# bontor_mbed_lowpan_rev_g.net
KiCad netlist of a schematic drawn in EAGLE
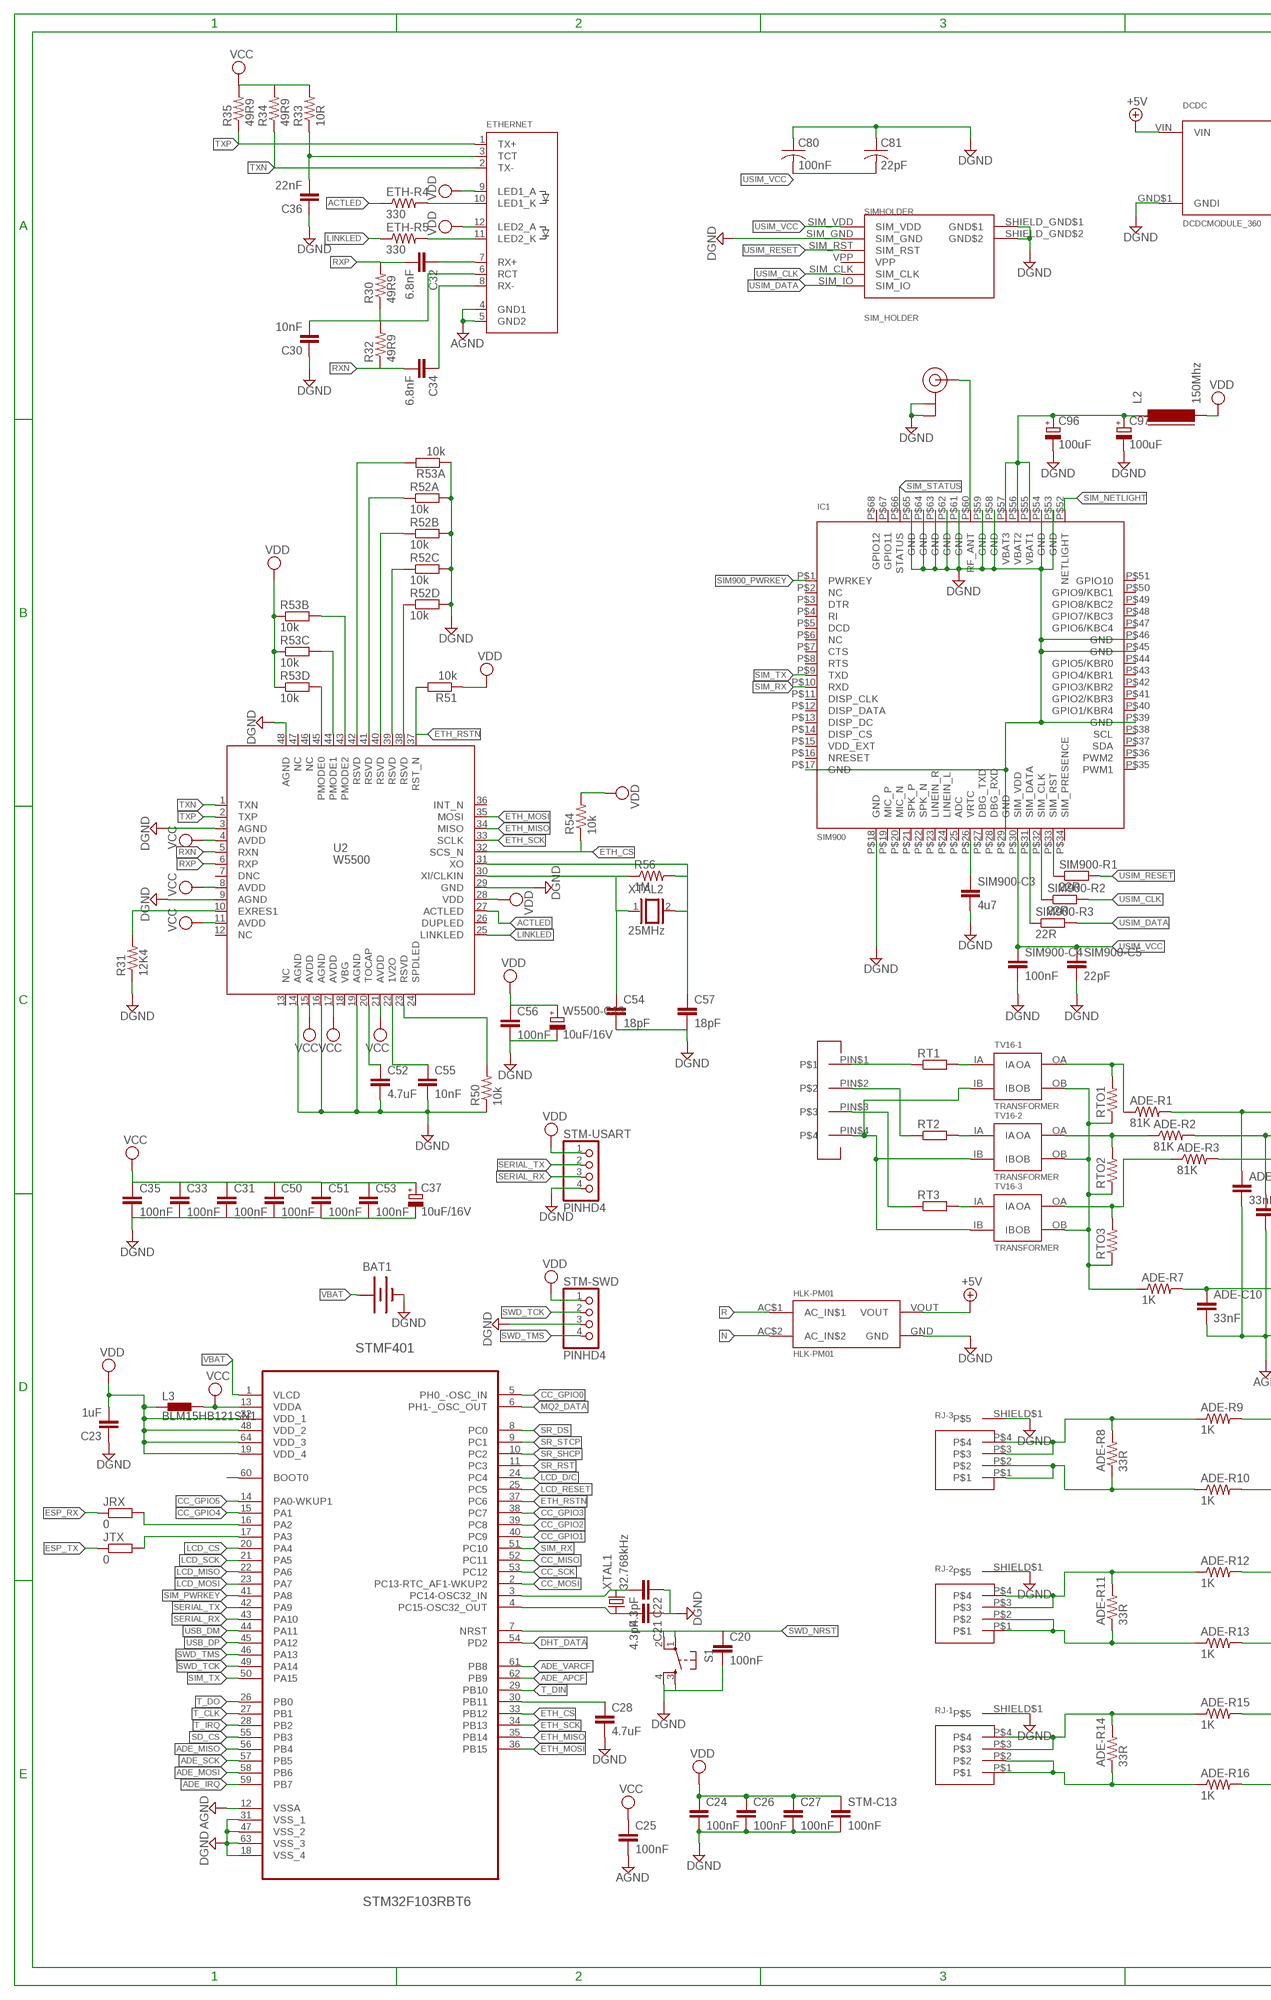
[diagram p0: schematic, sheet 1, part 1 of 2]
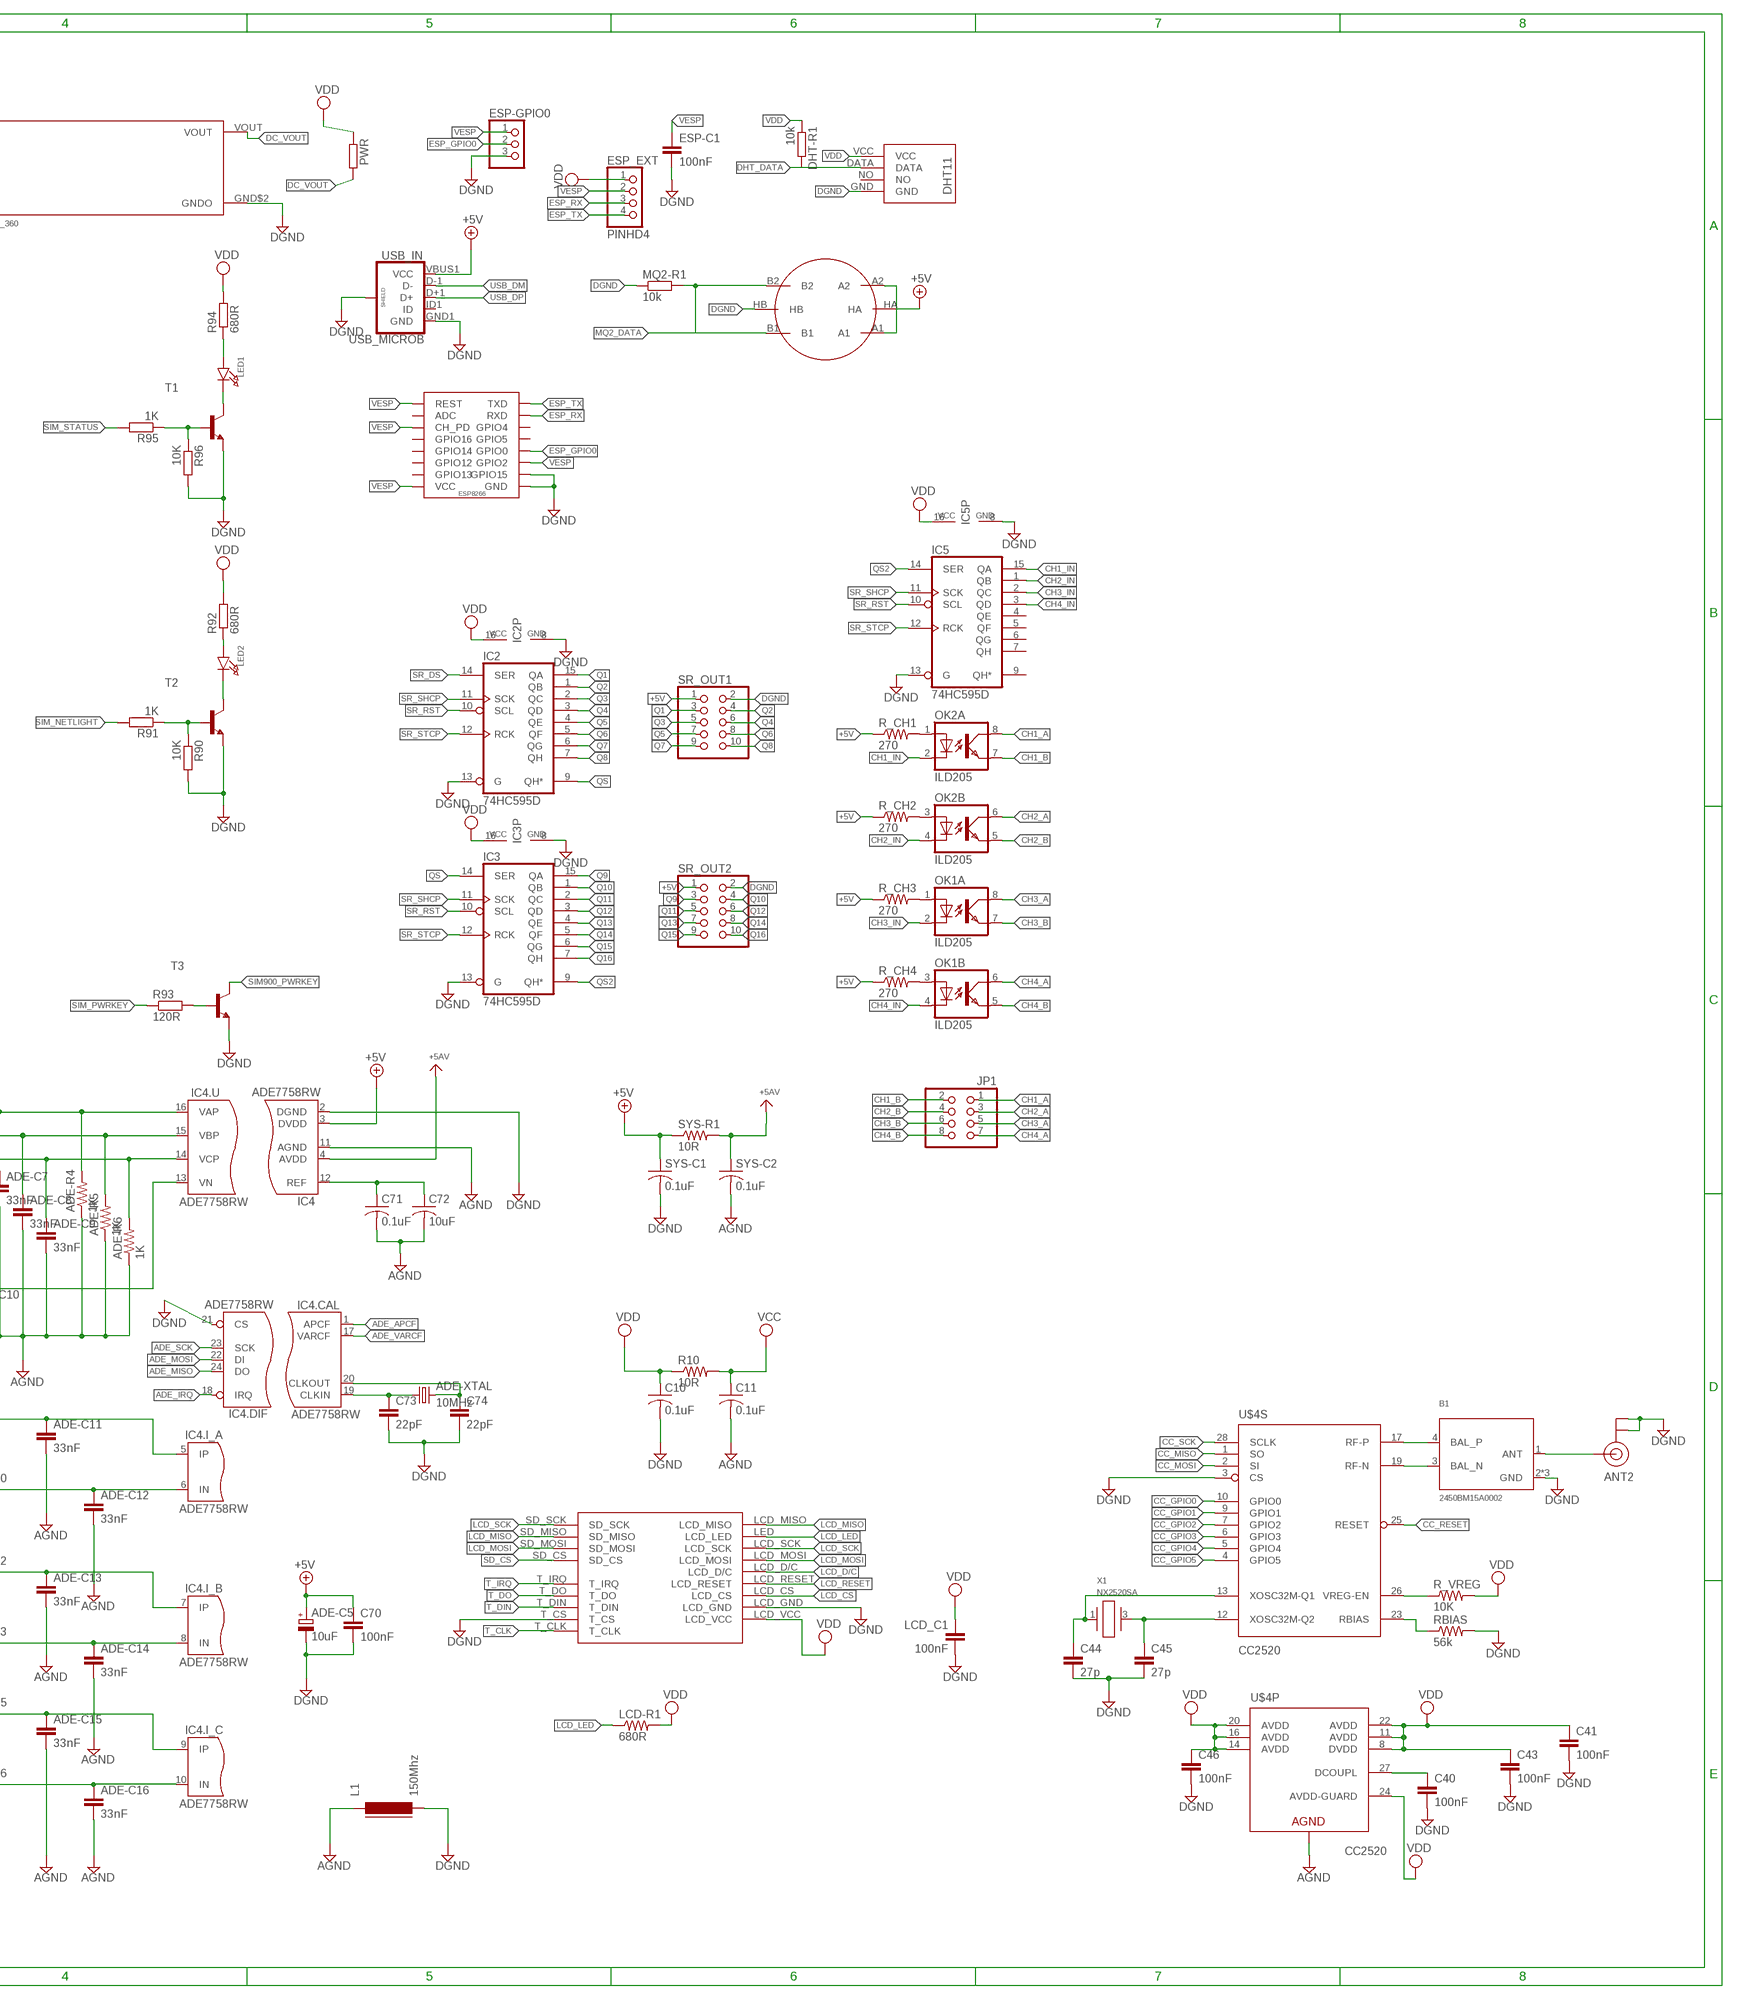
[diagram p1: schematic, sheet 1, part 2 of 2]

(export (version "E")
  (design (tool "Eeschema 10.0.6"))
  (components
    (comp (ref "ADE-C5")
      (value "10uF")
      (footprint "eagle-import:153CLV-0605")
      (libsource (lib "eagle-import") (part "CPOL-EU153CLV-0605"))
    )
    (comp (ref "ADE-C7")
      (value "33nF")
      (footprint "eagle-import:0603-CAP")
      (libsource (lib "eagle-import") (part "CAP0603-CAP"))
    )
    (comp (ref "ADE-C8")
      (value "33nF")
      (footprint "eagle-import:0603-CAP")
      (libsource (lib "eagle-import") (part "CAP0603-CAP"))
    )
    (comp (ref "ADE-C9")
      (value "33nF")
      (footprint "eagle-import:0603-CAP")
      (libsource (lib "eagle-import") (part "CAP0603-CAP"))
    )
    (comp (ref "ADE-C10")
      (value "33nF")
      (footprint "eagle-import:0603-CAP")
      (libsource (lib "eagle-import") (part "CAP0603-CAP"))
    )
    (comp (ref "ADE-C11")
      (value "33nF")
      (footprint "eagle-import:0402-CAP")
      (libsource (lib "eagle-import") (part "CAP0402-CAP"))
    )
    (comp (ref "ADE-C12")
      (value "33nF")
      (footprint "eagle-import:0402-CAP")
      (libsource (lib "eagle-import") (part "CAP0402-CAP"))
    )
    (comp (ref "ADE-C13")
      (value "33nF")
      (footprint "eagle-import:0402-CAP")
      (libsource (lib "eagle-import") (part "CAP0402-CAP"))
    )
    (comp (ref "ADE-C14")
      (value "33nF")
      (footprint "eagle-import:0402-CAP")
      (libsource (lib "eagle-import") (part "CAP0402-CAP"))
    )
    (comp (ref "ADE-C15")
      (value "33nF")
      (footprint "eagle-import:0402-CAP")
      (libsource (lib "eagle-import") (part "CAP0402-CAP"))
    )
    (comp (ref "ADE-C16")
      (value "33nF")
      (footprint "eagle-import:0402-CAP")
      (libsource (lib "eagle-import") (part "CAP0402-CAP"))
    )
    (comp (ref "ADE-R1")
      (value "81K")
      (footprint "eagle-import:0603-RES")
      (libsource (lib "eagle-import") (part "RESISTOR0603-RES"))
    )
    (comp (ref "ADE-R2")
      (value "81K")
      (footprint "eagle-import:0603-RES")
      (libsource (lib "eagle-import") (part "RESISTOR0603-RES"))
    )
    (comp (ref "ADE-R3")
      (value "81K")
      (footprint "eagle-import:0603-RES")
      (libsource (lib "eagle-import") (part "RESISTOR0603-RES"))
    )
    (comp (ref "ADE-R4")
      (value "1K")
      (footprint "eagle-import:0603-RES")
      (libsource (lib "eagle-import") (part "RESISTOR0603-RES"))
    )
    (comp (ref "ADE-R5")
      (value "1K")
      (footprint "eagle-import:0603-RES")
      (libsource (lib "eagle-import") (part "RESISTOR0603-RES"))
    )
    (comp (ref "ADE-R6")
      (value "1K")
      (footprint "eagle-import:0603-RES")
      (libsource (lib "eagle-import") (part "RESISTOR0603-RES"))
    )
    (comp (ref "ADE-R7")
      (value "1K")
      (footprint "eagle-import:0603-RES")
      (libsource (lib "eagle-import") (part "RESISTOR0603-RES"))
    )
    (comp (ref "ADE-R8")
      (value "33R")
      (footprint "eagle-import:0402-RES")
      (libsource (lib "eagle-import") (part "RESISTOR0402-RES"))
    )
    (comp (ref "ADE-R9")
      (value "1K")
      (footprint "eagle-import:0402-RES")
      (libsource (lib "eagle-import") (part "RESISTOR0402-RES"))
    )
    (comp (ref "ADE-R10")
      (value "1K")
      (footprint "eagle-import:0402-RES")
      (libsource (lib "eagle-import") (part "RESISTOR0402-RES"))
    )
    (comp (ref "ADE-R11")
      (value "33R")
      (footprint "eagle-import:0402-RES")
      (libsource (lib "eagle-import") (part "RESISTOR0402-RES"))
    )
    (comp (ref "ADE-R12")
      (value "1K")
      (footprint "eagle-import:0402-RES")
      (libsource (lib "eagle-import") (part "RESISTOR0402-RES"))
    )
    (comp (ref "ADE-R13")
      (value "1K")
      (footprint "eagle-import:0402-RES")
      (libsource (lib "eagle-import") (part "RESISTOR0402-RES"))
    )
    (comp (ref "ADE-R14")
      (value "33R")
      (footprint "eagle-import:0402-RES")
      (libsource (lib "eagle-import") (part "RESISTOR0402-RES"))
    )
    (comp (ref "ADE-R15")
      (value "1K")
      (footprint "eagle-import:0402-RES")
      (libsource (lib "eagle-import") (part "RESISTOR0402-RES"))
    )
    (comp (ref "ADE-R16")
      (value "1K")
      (footprint "eagle-import:0402-RES")
      (libsource (lib "eagle-import") (part "RESISTOR0402-RES"))
    )
    (comp (ref "ADE-XTAL")
      (value "10MHz")
      (footprint "eagle-import:HC49US")
      (libsource (lib "eagle-import") (part "CRYSTALHC49US"))
    )
    (comp (ref "ANT1")
      (value "U.FL")
      (footprint "eagle-import:U.FL")
      (libsource (lib "eagle-import") (part "U.FL"))
    )
    (comp (ref "ANT2")
      (value "U.FL")
      (footprint "eagle-import:U.FL")
      (libsource (lib "eagle-import") (part "SparkFun-Connectors_U.FL"))
    )
    (comp (ref "B1")
      (value "2450BM15A0002")
      (footprint "eagle-import:2450BM")
      (libsource (lib "eagle-import") (part "2450BM15A0002"))
    )
    (comp (ref "BAT1")
      (value "BATTERY12MM")
      (footprint "eagle-import:BATTCON_12MM")
      (libsource (lib "eagle-import") (part "BATTERY12MM"))
    )
    (comp (ref "C10")
      (value "0.1uF")
      (footprint "eagle-import:C0603@1")
      (libsource (lib "eagle-import") (part "C-USC0603"))
    )
    (comp (ref "C11")
      (value "0.1uF")
      (footprint "eagle-import:C0603@1")
      (libsource (lib "eagle-import") (part "C-USC0603"))
    )
    (comp (ref "C20")
      (value "100nF")
      (footprint "eagle-import:C0603")
      (libsource (lib "eagle-import") (part "C-EUC0603"))
    )
    (comp (ref "C21")
      (value "4.3pF")
      (footprint "eagle-import:C0603")
      (libsource (lib "eagle-import") (part "C-EUC0603"))
    )
    (comp (ref "C22")
      (value "4.3pF")
      (footprint "eagle-import:C0603")
      (libsource (lib "eagle-import") (part "C-EUC0603"))
    )
    (comp (ref "C23")
      (value "1uF")
      (footprint "eagle-import:C0603")
      (libsource (lib "eagle-import") (part "C-EUC0603"))
    )
    (comp (ref "C24")
      (value "100nF")
      (footprint "eagle-import:C0603")
      (libsource (lib "eagle-import") (part "C-EUC0603"))
    )
    (comp (ref "C25")
      (value "100nF")
      (footprint "eagle-import:C0603")
      (libsource (lib "eagle-import") (part "C-EUC0603"))
    )
    (comp (ref "C26")
      (value "100nF")
      (footprint "eagle-import:C0603")
      (libsource (lib "eagle-import") (part "C-EUC0603"))
    )
    (comp (ref "C27")
      (value "100nF")
      (footprint "eagle-import:C0402")
      (libsource (lib "eagle-import") (part "C-EUC0402"))
    )
    (comp (ref "C28")
      (value "4.7uF")
      (footprint "eagle-import:C0603")
      (libsource (lib "eagle-import") (part "C-EUC0603"))
    )
    (comp (ref "C30")
      (value "10nF")
      (footprint "eagle-import:C0603")
      (libsource (lib "eagle-import") (part "C-EUC0603"))
    )
    (comp (ref "C31")
      (value "100nF")
      (footprint "eagle-import:C0603")
      (libsource (lib "eagle-import") (part "C-EUC0603"))
    )
    (comp (ref "C32")
      (value "6.8nF")
      (footprint "eagle-import:C0603")
      (libsource (lib "eagle-import") (part "C-EUC0603"))
    )
    (comp (ref "C33")
      (value "100nF")
      (footprint "eagle-import:C0603")
      (libsource (lib "eagle-import") (part "C-EUC0603"))
    )
    (comp (ref "C34")
      (value "6.8nF")
      (footprint "eagle-import:C0603")
      (libsource (lib "eagle-import") (part "C-EUC0603"))
    )
    (comp (ref "C35")
      (value "100nF")
      (footprint "eagle-import:C0603")
      (libsource (lib "eagle-import") (part "C-EUC0603"))
    )
    (comp (ref "C36")
      (value "22nF")
      (footprint "eagle-import:C0603")
      (libsource (lib "eagle-import") (part "C-EUC0603"))
    )
    (comp (ref "C37")
      (value "10uF/16V")
      (footprint "eagle-import:153CLV-0605")
      (libsource (lib "eagle-import") (part "CPOL-EU153CLV-0605"))
    )
    (comp (ref "C40")
      (value "100nF")
      (footprint "eagle-import:C0402")
      (libsource (lib "eagle-import") (part "C-EUC0402"))
    )
    (comp (ref "C41")
      (value "100nF")
      (footprint "eagle-import:C0402")
      (libsource (lib "eagle-import") (part "C-EUC0402"))
    )
    (comp (ref "C43")
      (value "100nF")
      (footprint "eagle-import:C0402")
      (libsource (lib "eagle-import") (part "C-EUC0402"))
    )
    (comp (ref "C44")
      (value "27p")
      (footprint "eagle-import:C0201")
      (libsource (lib "eagle-import") (part "C-EUC0201"))
    )
    (comp (ref "C45")
      (value "27p")
      (footprint "eagle-import:C0201")
      (libsource (lib "eagle-import") (part "C-EUC0201"))
    )
    (comp (ref "C46")
      (value "100nF")
      (footprint "eagle-import:C0402")
      (libsource (lib "eagle-import") (part "C-EUC0402"))
    )
    (comp (ref "C50")
      (value "100nF")
      (footprint "eagle-import:C0603")
      (libsource (lib "eagle-import") (part "C-EUC0603"))
    )
    (comp (ref "C51")
      (value "100nF")
      (footprint "eagle-import:C0603")
      (libsource (lib "eagle-import") (part "C-EUC0603"))
    )
    (comp (ref "C52")
      (value "4.7uF")
      (footprint "eagle-import:C0603")
      (libsource (lib "eagle-import") (part "C-EUC0603"))
    )
    (comp (ref "C53")
      (value "100nF")
      (footprint "eagle-import:C0603")
      (libsource (lib "eagle-import") (part "C-EUC0603"))
    )
    (comp (ref "C54")
      (value "18pF")
      (footprint "eagle-import:C0603")
      (libsource (lib "eagle-import") (part "C-EUC0603"))
    )
    (comp (ref "C55")
      (value "10nF")
      (footprint "eagle-import:C0603")
      (libsource (lib "eagle-import") (part "C-EUC0603"))
    )
    (comp (ref "C56")
      (value "100nF")
      (footprint "eagle-import:C0603")
      (libsource (lib "eagle-import") (part "C-EUC0603"))
    )
    (comp (ref "C57")
      (value "18pF")
      (footprint "eagle-import:C0603")
      (libsource (lib "eagle-import") (part "C-EUC0603"))
    )
    (comp (ref "C70")
      (value "100nF")
      (footprint "eagle-import:C0603")
      (libsource (lib "eagle-import") (part "C-EUC0603"))
    )
    (comp (ref "C71")
      (value "0.1uF")
      (footprint "eagle-import:C0603@1")
      (libsource (lib "eagle-import") (part "C-USC0603"))
    )
    (comp (ref "C72")
      (value "10uF")
      (footprint "eagle-import:C0805K")
      (libsource (lib "eagle-import") (part "C-USC0805K"))
    )
    (comp (ref "C73")
      (value "22pF")
      (footprint "eagle-import:C0603")
      (libsource (lib "eagle-import") (part "C-EUC0603"))
    )
    (comp (ref "C74")
      (value "22pF")
      (footprint "eagle-import:C0603")
      (libsource (lib "eagle-import") (part "C-EUC0603"))
    )
    (comp (ref "C80")
      (value "100nF")
      (footprint "eagle-import:C0603K")
      (libsource (lib "eagle-import") (part "C-USC0603K"))
    )
    (comp (ref "C81")
      (value "22pF")
      (footprint "eagle-import:C0603K")
      (libsource (lib "eagle-import") (part "C-USC0603K"))
    )
    (comp (ref "C96")
      (value "100uF")
      (footprint "eagle-import:153CLV-0605")
      (libsource (lib "eagle-import") (part "CPOL-EU153CLV-0605"))
    )
    (comp (ref "C97")
      (value "100uF")
      (footprint "eagle-import:153CLV-0605")
      (libsource (lib "eagle-import") (part "CPOL-EU153CLV-0605"))
    )
    (comp (ref "DCDC")
      (value "DCDCMODULE_360")
      (footprint "eagle-import:DCDCMODULE-360")
      (libsource (lib "eagle-import") (part "DCDCMODULE_360"))
    )
    (comp (ref "DHT-R1")
      (value "10k")
      (footprint "eagle-import:R0603")
      (libsource (lib "eagle-import") (part "resistor_R-EU_R0603"))
    )
    (comp (ref "ESP")
      (value "ESP")
      (footprint "eagle-import:WI12")
      (libsource (lib "eagle-import") (part "ESP8266WI12"))
    )
    (comp (ref "ESP-C1")
      (value "100nF")
      (footprint "eagle-import:C0603")
      (libsource (lib "eagle-import") (part "C-EUC0603"))
    )
    (comp (ref "ESP-GPIO0")
      (value "PINHD-1X3")
      (footprint "eagle-import:1X03")
      (libsource (lib "eagle-import") (part "PINHD-1X3"))
    )
    (comp (ref "ESP_EXT")
      (value "PINHD4")
      (footprint "eagle-import:PINHD4")
      (libsource (lib "eagle-import") (part "PINHD4"))
    )
    (comp (ref "ETH-R4")
      (value "330")
      (footprint "eagle-import:R0603")
      (libsource (lib "eagle-import") (part "resistor_R-US_R0603"))
    )
    (comp (ref "ETH-R5")
      (value "330")
      (footprint "eagle-import:R0603")
      (libsource (lib "eagle-import") (part "resistor_R-US_R0603"))
    )
    (comp (ref "ETHERNET")
      (value "RJ45J0026D21BNL")
      (footprint "eagle-import:RJ45_PULSEJACK")
      (libsource (lib "eagle-import") (part "RJ45J0026D21BNL"))
    )
    (comp (ref "HLK-PM01")
      (value "HLK-PM01")
      (footprint "eagle-import:HLK-PM01")
      (libsource (lib "eagle-import") (part "HLK-PM01"))
    )
    (comp (ref "IC1")
      (value "SIM900")
      (footprint "eagle-import:SIM900_SMT")
      (libsource (lib "eagle-import") (part "GSM_SIM900_LITERAL"))
    )
    (comp (ref "IC2")
      (value "74HC595D")
      (footprint "eagle-import:SO16")
      (libsource (lib "eagle-import") (part "74595DHC"))
    )
    (comp (ref "IC3")
      (value "74HC595D")
      (footprint "eagle-import:SO16")
      (libsource (lib "eagle-import") (part "74595DHC"))
    )
    (comp (ref "IC4")
      (value "ADE7758RW")
      (footprint "eagle-import:SOIC24")
      (libsource (lib "eagle-import") (part "ADE7758RW"))
    )
    (comp (ref "IC5")
      (value "74HC595D")
      (footprint "eagle-import:SO16")
      (libsource (lib "eagle-import") (part "74595DHC"))
    )
    (comp (ref "JP1")
      (value "PINHD-2X4")
      (footprint "eagle-import:2X04")
      (libsource (lib "eagle-import") (part "PINHD-2X4"))
    )
    (comp (ref "JRX")
      (value "0")
      (footprint "eagle-import:R0201")
      (libsource (lib "eagle-import") (part "R-EU_R0201"))
    )
    (comp (ref "JTX")
      (value "0")
      (footprint "eagle-import:R0201")
      (libsource (lib "eagle-import") (part "R-EU_R0201"))
    )
    (comp (ref "L1")
      (value "150Mhz")
      (footprint "eagle-import:FB805")
      (libsource (lib "eagle-import") (part "FERRITE-0805"))
    )
    (comp (ref "L2")
      (value "150Mhz")
      (footprint "eagle-import:FB805")
      (libsource (lib "eagle-import") (part "FERRITE-0805"))
    )
    (comp (ref "L3")
      (value "BLM15HB121SN1")
      (footprint "eagle-import:0402")
      (libsource (lib "eagle-import") (part "BLM15HB121SN1"))
    )
    (comp (ref "LCD-R1")
      (value "680R")
      (footprint "eagle-import:0603-RES")
      (libsource (lib "eagle-import") (part "RESISTOR0603-RES"))
    )
    (comp (ref "LCD14")
      (value "LCD_2.4")
      (footprint "eagle-import:LCD_TOUCH_2-4")
      (libsource (lib "eagle-import") (part "LCD_2.4"))
    )
    (comp (ref "LCD_C1")
      (value "100nF")
      (footprint "eagle-import:C0603")
      (libsource (lib "eagle-import") (part "C-EUC0603"))
    )
    (comp (ref "LED1")
      (value "LED0805_NOOUTLINE")
      (footprint "eagle-import:CHIPLED_0805_NOOUTLINE")
      (libsource (lib "eagle-import") (part "LED0805_NOOUTLINE"))
    )
    (comp (ref "LED2")
      (value "LED0805_NOOUTLINE")
      (footprint "eagle-import:CHIPLED_0805_NOOUTLINE")
      (libsource (lib "eagle-import") (part "LED0805_NOOUTLINE"))
    )
    (comp (ref "MQ2-R1")
      (value "10k")
      (footprint "eagle-import:R0603")
      (libsource (lib "eagle-import") (part "resistor_R-EU_R0603"))
    )
    (comp (ref "OK1")
      (value "ILD205")
      (footprint "eagle-import:SOIC08")
      (fields (field (name "MF") "VISHAY/TELEFUNKEN") (field (name "MPN") "ILD205T"))
      (libsource (lib "eagle-import") (part "ILD205"))
    )
    (comp (ref "OK2")
      (value "ILD205")
      (footprint "eagle-import:SOIC08")
      (fields (field (name "MF") "VISHAY/TELEFUNKEN") (field (name "MPN") "ILD205T"))
      (libsource (lib "eagle-import") (part "ILD205"))
    )
    (comp (ref "PWR")
      (value "R-EU_R0402")
      (footprint "eagle-import:R0402")
      (libsource (lib "eagle-import") (part "R-EU_R0402"))
    )
    (comp (ref "R10")
      (value "10R")
      (footprint "eagle-import:0603-RES")
      (libsource (lib "eagle-import") (part "RESISTOR0603-RES"))
    )
    (comp (ref "R30")
      (value "49R9")
      (footprint "eagle-import:R0603")
      (libsource (lib "eagle-import") (part "resistor_R-US_R0603"))
    )
    (comp (ref "R31")
      (value "12K4")
      (footprint "eagle-import:R0805")
      (libsource (lib "eagle-import") (part "resistor_R-US_R0805"))
    )
    (comp (ref "R32")
      (value "49R9")
      (footprint "eagle-import:R0603")
      (libsource (lib "eagle-import") (part "resistor_R-US_R0603"))
    )
    (comp (ref "R33")
      (value "10R")
      (footprint "eagle-import:R0603")
      (libsource (lib "eagle-import") (part "resistor_R-US_R0603"))
    )
    (comp (ref "R34")
      (value "49R9")
      (footprint "eagle-import:R0603")
      (libsource (lib "eagle-import") (part "resistor_R-US_R0603"))
    )
    (comp (ref "R35")
      (value "49R9")
      (footprint "eagle-import:R0603")
      (libsource (lib "eagle-import") (part "resistor_R-US_R0603"))
    )
    (comp (ref "R50")
      (value "10k")
      (footprint "eagle-import:R0603")
      (libsource (lib "eagle-import") (part "resistor_R-US_R0603"))
    )
    (comp (ref "R51")
      (value "10k")
      (footprint "eagle-import:R0603")
      (libsource (lib "eagle-import") (part "R-EU_R0603"))
    )
    (comp (ref "R52")
      (value "10k")
      (footprint "eagle-import:RN8P-4R-CRA06S")
      (libsource (lib "eagle-import") (part "RESISTOR_ARRAY_4"))
    )
    (comp (ref "R53")
      (value "10k")
      (footprint "eagle-import:RN8P-4R-CRA06S")
      (libsource (lib "eagle-import") (part "RESISTOR_ARRAY_4"))
    )
    (comp (ref "R54")
      (value "10k")
      (footprint "eagle-import:R0603")
      (libsource (lib "eagle-import") (part "resistor_R-US_R0603"))
    )
    (comp (ref "R56")
      (value "1M")
      (footprint "eagle-import:R0603")
      (libsource (lib "eagle-import") (part "resistor_R-US_R0603"))
    )
    (comp (ref "R90")
      (value "10K")
      (footprint "eagle-import:R0603")
      (libsource (lib "eagle-import") (part "R-EU_R0603"))
    )
    (comp (ref "R91")
      (value "1K")
      (footprint "eagle-import:R0603")
      (libsource (lib "eagle-import") (part "R-EU_R0603"))
    )
    (comp (ref "R92")
      (value "680R")
      (footprint "eagle-import:R0603")
      (libsource (lib "eagle-import") (part "R-EU_R0603"))
    )
    (comp (ref "R93")
      (value "120R")
      (footprint "eagle-import:R0603")
      (libsource (lib "eagle-import") (part "resistor_R-EU_R0603"))
    )
    (comp (ref "R94")
      (value "680R")
      (footprint "eagle-import:R0603")
      (libsource (lib "eagle-import") (part "R-EU_R0603"))
    )
    (comp (ref "R95")
      (value "1K")
      (footprint "eagle-import:R0603")
      (libsource (lib "eagle-import") (part "R-EU_R0603"))
    )
    (comp (ref "R96")
      (value "10K")
      (footprint "eagle-import:R0603")
      (libsource (lib "eagle-import") (part "R-EU_R0603"))
    )
    (comp (ref "RBIAS")
      (value "56k")
      (footprint "eagle-import:0402-RES")
      (libsource (lib "eagle-import") (part "RESISTOR0402-RES"))
    )
    (comp (ref "RJ-1")
      (value "RJ11-4P-V")
      (footprint "eagle-import:RJ11-4P-V")
      (libsource (lib "eagle-import") (part "RJ11-4P-V"))
    )
    (comp (ref "RJ-2")
      (value "RJ11-4P-V")
      (footprint "eagle-import:RJ11-4P-V")
      (libsource (lib "eagle-import") (part "RJ11-4P-V"))
    )
    (comp (ref "RJ-3")
      (value "RJ11-4P-V")
      (footprint "eagle-import:RJ11-4P-V")
      (libsource (lib "eagle-import") (part "RJ11-4P-V"))
    )
    (comp (ref "RT1")
      (value "R-EU_0309/V")
      (footprint "eagle-import:0309V")
      (libsource (lib "eagle-import") (part "R-EU_0309/V"))
    )
    (comp (ref "RT2")
      (value "R-EU_0309/V")
      (footprint "eagle-import:0309V")
      (libsource (lib "eagle-import") (part "R-EU_0309/V"))
    )
    (comp (ref "RT3")
      (value "R-EU_0309/V")
      (footprint "eagle-import:0309V")
      (libsource (lib "eagle-import") (part "R-EU_0309/V"))
    )
    (comp (ref "RTO1")
      (value "R-US_0309_12")
      (footprint "eagle-import:0309_12")
      (libsource (lib "eagle-import") (part "R-US_0309_12"))
    )
    (comp (ref "RTO2")
      (value "R-US_0309_12")
      (footprint "eagle-import:0309_12")
      (libsource (lib "eagle-import") (part "R-US_0309_12"))
    )
    (comp (ref "RTO3")
      (value "R-US_0309_12")
      (footprint "eagle-import:0309_12")
      (libsource (lib "eagle-import") (part "R-US_0309_12"))
    )
    (comp (ref "R_CH1")
      (value "270")
      (footprint "eagle-import:0603-RES")
      (libsource (lib "eagle-import") (part "RESISTOR0603-RES"))
    )
    (comp (ref "R_CH2")
      (value "270")
      (footprint "eagle-import:0603-RES")
      (libsource (lib "eagle-import") (part "RESISTOR0603-RES"))
    )
    (comp (ref "R_CH3")
      (value "270")
      (footprint "eagle-import:0603-RES")
      (libsource (lib "eagle-import") (part "RESISTOR0603-RES"))
    )
    (comp (ref "R_CH4")
      (value "270")
      (footprint "eagle-import:0603-RES")
      (libsource (lib "eagle-import") (part "RESISTOR0603-RES"))
    )
    (comp (ref "R_VREG")
      (value "10K")
      (footprint "eagle-import:0402-RES")
      (libsource (lib "eagle-import") (part "RESISTOR0402-RES"))
    )
    (comp (ref "S1")
      (value "TAC_SWITCHPTH")
      (footprint "eagle-import:TACTILE-PTH")
      (libsource (lib "eagle-import") (part "TAC_SWITCHPTH"))
    )
    (comp (ref "SENSOR-MQ2")
      (value "METHANE_SENSOR")
      (footprint "eagle-import:MQ-3")
      (libsource (lib "eagle-import") (part "METHANE_SENSOR"))
    )
    (comp (ref "SIM900-C3")
      (value "4u7")
      (footprint "eagle-import:C0603")
      (libsource (lib "eagle-import") (part "C-EUC0603"))
    )
    (comp (ref "SIM900-C4")
      (value "100nF")
      (footprint "eagle-import:C0603")
      (libsource (lib "eagle-import") (part "C-EUC0603"))
    )
    (comp (ref "SIM900-C5")
      (value "22pF")
      (footprint "eagle-import:C0603")
      (libsource (lib "eagle-import") (part "C-EUC0603"))
    )
    (comp (ref "SIM900-R1")
      (value "22R")
      (footprint "eagle-import:R0603")
      (libsource (lib "eagle-import") (part "R-EU_R0603"))
    )
    (comp (ref "SIM900-R2")
      (value "22R")
      (footprint "eagle-import:R0603")
      (libsource (lib "eagle-import") (part "R-EU_R0603"))
    )
    (comp (ref "SIM900-R3")
      (value "22R")
      (footprint "eagle-import:R0603")
      (libsource (lib "eagle-import") (part "R-EU_R0603"))
    )
    (comp (ref "SIMHOLDER")
      (value "SIM_HOLDER")
      (footprint "eagle-import:SIMHOLDER-PUSHPUSH")
      (libsource (lib "eagle-import") (part "SIM_HOLDER"))
    )
    (comp (ref "SR_OUT1")
      (value "PINHD-2X5")
      (footprint "eagle-import:2X05")
      (libsource (lib "eagle-import") (part "PINHD-2X5"))
    )
    (comp (ref "SR_OUT2")
      (value "PINHD-2X5")
      (footprint "eagle-import:2X05")
      (libsource (lib "eagle-import") (part "PINHD-2X5"))
    )
    (comp (ref "STM-C13")
      (value "100nF")
      (footprint "eagle-import:C0603")
      (libsource (lib "eagle-import") (part "C-EUC0603"))
    )
    (comp (ref "STM-SWD")
      (value "PINHD4")
      (footprint "eagle-import:PINHD4")
      (libsource (lib "eagle-import") (part "PINHD4"))
    )
    (comp (ref "STM-USART")
      (value "PINHD4")
      (footprint "eagle-import:PINHD4")
      (libsource (lib "eagle-import") (part "PINHD4"))
    )
    (comp (ref "STMF401")
      (value "STM32F103RBT6")
      (footprint "eagle-import:QFP50P1200X1200X160-64N")
      (fields (field (name "MPN") "STM32L152RBT6"))
      (libsource (lib "eagle-import") (part "STM32L152RBT6"))
    )
    (comp (ref "SYS-C1")
      (value "0.1uF")
      (footprint "eagle-import:C0603@1")
      (libsource (lib "eagle-import") (part "C-USC0603"))
    )
    (comp (ref "SYS-C2")
      (value "0.1uF")
      (footprint "eagle-import:C0603@1")
      (libsource (lib "eagle-import") (part "C-USC0603"))
    )
    (comp (ref "SYS-R1")
      (value "10R")
      (footprint "eagle-import:0603-RES")
      (libsource (lib "eagle-import") (part "RESISTOR0603-RES"))
    )
    (comp (ref "T1")
      (value "MMBT2222ALT1-NPN-SOT23-BEC")
      (footprint "eagle-import:SOT23-BEC")
      (libsource (lib "eagle-import") (part "-NPN-SOT23-BECMMBT2222ALT1"))
    )
    (comp (ref "T2")
      (value "MMBT2222ALT1-NPN-SOT23-BEC")
      (footprint "eagle-import:SOT23-BEC")
      (libsource (lib "eagle-import") (part "-NPN-SOT23-BECMMBT2222ALT1"))
    )
    (comp (ref "T3")
      (value "MMBT2222ALT1-NPN-SOT23-BEC")
      (footprint "eagle-import:SOT23-BEC")
      (libsource (lib "eagle-import") (part "transistor-neu-to92_-NPN-SOT23-BECMMBT2222ALT1"))
    )
    (comp (ref "TERM_BLOCK")
      (value "TERMINAL_BLOCK_TW")
      (footprint "eagle-import:TERMINAL-TWO-WAY")
      (libsource (lib "eagle-import") (part "TERMINAL_BLOCK_TW"))
    )
    (comp (ref "TV16-1")
      (value "TRANSFORMER")
      (footprint "eagle-import:TV16")
      (libsource (lib "eagle-import") (part "TRANSFORMER"))
    )
    (comp (ref "TV16-2")
      (value "TRANSFORMER")
      (footprint "eagle-import:TV16")
      (libsource (lib "eagle-import") (part "TRANSFORMER"))
    )
    (comp (ref "TV16-3")
      (value "TRANSFORMER")
      (footprint "eagle-import:TV16")
      (libsource (lib "eagle-import") (part "TRANSFORMER"))
    )
    (comp (ref "U$4")
      (value "CC2520")
      (footprint "eagle-import:QFN50P500X500X100-29N")
      (libsource (lib "eagle-import") (part "CC2520"))
    )
    (comp (ref "U$17")
      (value "DHT11")
      (footprint "eagle-import:DHT11")
      (libsource (lib "eagle-import") (part "DHT11"))
    )
    (comp (ref "U2")
      (value "W5500")
      (footprint "eagle-import:W5500")
      (libsource (lib "eagle-import") (part "W5500"))
    )
    (comp (ref "USB_IN")
      (value "USB_MICROB")
      (footprint "eagle-import:USB-B-MICRO-SMD_V03")
      (libsource (lib "eagle-import") (part "USB_MICROB_PLUGCONN-11752"))
    )
    (comp (ref "W5500-C13")
      (value "10uF/16V")
      (footprint "eagle-import:153CLV-0605")
      (libsource (lib "eagle-import") (part "CPOL-EU153CLV-0605"))
    )
    (comp (ref "X1")
      (value "NX2520SA")
      (footprint "eagle-import:NX2520SA")
      (libsource (lib "eagle-import") (part "NX2520SA"))
    )
    (comp (ref "XTAL1")
      (value "32.768kHz")
      (footprint "eagle-import:TC26H")
      (libsource (lib "eagle-import") (part "CRYSTALTC26H"))
    )
    (comp (ref "XTAL2")
      (value "25MHz")
      (footprint "eagle-import:QS")
      (libsource (lib "eagle-import") (part "XTAL/S"))
    )
  )
  (nets
    (net (code "1") (name "+5AV") (class "Default")
      (node (ref "IC4") (pin "4") (pinfunction "AVDD_4") (pintype "power_in"))
      (node (ref "SYS-C2") (pin "1") (pinfunction "1_1") (pintype "passive"))
      (node (ref "SYS-R1") (pin "2") (pinfunction "2_2") (pintype "passive"))
    )
    (net (code "2") (name "+5V") (class "Default")
      (node (ref "ADE-C5") (pin "+") (pinfunction "+_+") (pintype "passive"))
      (node (ref "C70") (pin "1") (pinfunction "1_1") (pintype "passive"))
      (node (ref "DCDC") (pin "VIN") (pinfunction "VIN_VIN") (pintype "bidirectional"))
      (node (ref "HLK-PM01") (pin "VOUT") (pinfunction "VOUT_VOUT") (pintype "bidirectional"))
      (node (ref "IC4") (pin "3") (pinfunction "DVDD_3") (pintype "power_in"))
      (node (ref "R_CH1") (pin "1") (pinfunction "1_1") (pintype "passive"))
      (node (ref "R_CH2") (pin "1") (pinfunction "1_1") (pintype "passive"))
      (node (ref "R_CH3") (pin "1") (pinfunction "1_1") (pintype "passive"))
      (node (ref "R_CH4") (pin "1") (pinfunction "1_1") (pintype "passive"))
      (node (ref "SENSOR-MQ2") (pin "A1") (pinfunction "A1_A1") (pintype "bidirectional"))
      (node (ref "SENSOR-MQ2") (pin "A2") (pinfunction "A2_A2") (pintype "bidirectional"))
      (node (ref "SENSOR-MQ2") (pin "HA") (pinfunction "HA_HA") (pintype "bidirectional"))
      (node (ref "SR_OUT1") (pin "1") (pinfunction "1_1") (pintype "passive"))
      (node (ref "SR_OUT2") (pin "1") (pinfunction "1_1") (pintype "passive"))
      (node (ref "SYS-C1") (pin "1") (pinfunction "1_1") (pintype "passive"))
      (node (ref "SYS-R1") (pin "1") (pinfunction "1_1") (pintype "passive"))
      (node (ref "USB_IN") (pin "VBUS1") (pinfunction "VCC_VBUS1") (pintype "bidirectional"))
    )
    (net (code "3") (name "/GPIO11") (class "Default")
      (node (ref "IC1") (pin "P$67") (pinfunction "GPIO11_P$67") (pintype "power_in"))
    )
    (net (code "4") (name "/GPIO12") (class "Default")
      (node (ref "IC1") (pin "P$68") (pinfunction "GPIO12_P$68") (pintype "power_in"))
    )
    (net (code "5") (name "ACTLED") (class "Default")
      (node (ref "ETH-R4") (pin "1") (pinfunction "1_1") (pintype "passive"))
      (node (ref "U2") (pin "27") (pinfunction "ACTLED_27") (pintype "passive"))
    )
    (net (code "6") (name "ADE_APCF") (class "Default")
      (node (ref "IC4") (pin "1") (pinfunction "APCF_1") (pintype "output"))
      (node (ref "STMF401") (pin "62") (pinfunction "PB9_62") (pintype "bidirectional"))
    )
    (net (code "7") (name "ADE_IRQ") (class "Default")
      (node (ref "IC4") (pin "18") (pinfunction "IRQ_18") (pintype "output"))
      (node (ref "STMF401") (pin "59") (pinfunction "PB7_59") (pintype "bidirectional"))
    )
    (net (code "8") (name "ADE_MISO") (class "Default")
      (node (ref "IC4") (pin "24") (pinfunction "DO_24") (pintype "output"))
      (node (ref "STMF401") (pin "56") (pinfunction "PB4_56") (pintype "bidirectional"))
    )
    (net (code "9") (name "ADE_MOSI") (class "Default")
      (node (ref "IC4") (pin "22") (pinfunction "DI_22") (pintype "input"))
      (node (ref "STMF401") (pin "58") (pinfunction "PB6_58") (pintype "bidirectional"))
    )
    (net (code "10") (name "ADE_SCK") (class "Default")
      (node (ref "IC4") (pin "23") (pinfunction "SCK_23") (pintype "input"))
      (node (ref "STMF401") (pin "57") (pinfunction "PB5_57") (pintype "bidirectional"))
    )
    (net (code "11") (name "ADE_VARCF") (class "Default")
      (node (ref "IC4") (pin "17") (pinfunction "VARCF_17") (pintype "output"))
      (node (ref "STMF401") (pin "61") (pinfunction "PB8_61") (pintype "bidirectional"))
    )
    (net (code "12") (name "AGND") (class "Default")
      (node (ref "ADE-C10") (pin "2") (pinfunction "2_2") (pintype "passive"))
      (node (ref "ADE-C11") (pin "2") (pinfunction "2_2") (pintype "passive"))
      (node (ref "ADE-C12") (pin "2") (pinfunction "2_2") (pintype "passive"))
      (node (ref "ADE-C13") (pin "2") (pinfunction "2_2") (pintype "passive"))
      (node (ref "ADE-C14") (pin "2") (pinfunction "2_2") (pintype "passive"))
      (node (ref "ADE-C15") (pin "2") (pinfunction "2_2") (pintype "passive"))
      (node (ref "ADE-C16") (pin "2") (pinfunction "2_2") (pintype "passive"))
      (node (ref "ADE-C7") (pin "2") (pinfunction "2_2") (pintype "passive"))
      (node (ref "ADE-C8") (pin "2") (pinfunction "2_2") (pintype "passive"))
      (node (ref "ADE-C9") (pin "2") (pinfunction "2_2") (pintype "passive"))
      (node (ref "ADE-R4") (pin "1") (pinfunction "1_1") (pintype "passive"))
      (node (ref "ADE-R5") (pin "1") (pinfunction "1_1") (pintype "passive"))
      (node (ref "ADE-R6") (pin "1") (pinfunction "1_1") (pintype "passive"))
      (node (ref "C11") (pin "2") (pinfunction "2_2") (pintype "passive"))
      (node (ref "C25") (pin "2") (pinfunction "2_2") (pintype "passive"))
      (node (ref "C71") (pin "2") (pinfunction "2_2") (pintype "passive"))
      (node (ref "C72") (pin "2") (pinfunction "2_2") (pintype "passive"))
      (node (ref "ETHERNET") (pin "4") (pinfunction "GND1_4") (pintype "bidirectional"))
      (node (ref "ETHERNET") (pin "5") (pinfunction "GND2_5") (pintype "bidirectional"))
      (node (ref "IC4") (pin "11") (pinfunction "AGND_11") (pintype "power_in"))
      (node (ref "L1") (pin "1") (pinfunction "1_1") (pintype "passive"))
      (node (ref "STMF401") (pin "12") (pinfunction "VSSA_12") (pintype "power_in"))
      (node (ref "SYS-C2") (pin "2") (pinfunction "2_2") (pintype "passive"))
      (node (ref "U$4") (pin "29") (pinfunction "AGND_29") (pintype "power_in"))
    )
    (net (code "13") (name "CC_GPIO0") (class "Default")
      (node (ref "STMF401") (pin "5") (pinfunction "PH0_-OSC_IN_5") (pintype "bidirectional"))
      (node (ref "U$4") (pin "10") (pinfunction "GPIO0_10") (pintype "output"))
    )
    (net (code "14") (name "CC_GPIO1") (class "Default")
      (node (ref "STMF401") (pin "40") (pinfunction "PC9_40") (pintype "bidirectional"))
      (node (ref "U$4") (pin "9") (pinfunction "GPIO1_9") (pintype "output"))
    )
    (net (code "15") (name "CC_GPIO2") (class "Default")
      (node (ref "STMF401") (pin "39") (pinfunction "PC8_39") (pintype "bidirectional"))
      (node (ref "U$4") (pin "7") (pinfunction "GPIO2_7") (pintype "bidirectional"))
    )
    (net (code "16") (name "CC_GPIO3") (class "Default")
      (node (ref "STMF401") (pin "38") (pinfunction "PC7_38") (pintype "bidirectional"))
      (node (ref "U$4") (pin "6") (pinfunction "GPIO3_6") (pintype "bidirectional"))
    )
    (net (code "17") (name "CC_GPIO4") (class "Default")
      (node (ref "STMF401") (pin "15") (pinfunction "PA1_15") (pintype "bidirectional"))
      (node (ref "U$4") (pin "5") (pinfunction "GPIO4_5") (pintype "bidirectional"))
    )
    (net (code "18") (name "CC_GPIO5") (class "Default")
      (node (ref "STMF401") (pin "14") (pinfunction "PA0-WKUP1_14") (pintype "bidirectional"))
      (node (ref "U$4") (pin "4") (pinfunction "GPIO5_4") (pintype "bidirectional"))
    )
    (net (code "19") (name "CC_MISO") (class "Default")
      (node (ref "STMF401") (pin "52") (pinfunction "PC11_52") (pintype "bidirectional"))
      (node (ref "U$4") (pin "1") (pinfunction "SO_1") (pintype "output"))
    )
    (net (code "20") (name "CC_MOSI") (class "Default")
      (node (ref "STMF401") (pin "2") (pinfunction "PC13-RTC_AF1-WKUP2_2") (pintype "bidirectional"))
      (node (ref "U$4") (pin "2") (pinfunction "SI_2") (pintype "input"))
    )
    (net (code "21") (name "CC_RESET") (class "Default")
      (node (ref "U$4") (pin "25") (pinfunction "RESET_25") (pintype "input"))
    )
    (net (code "22") (name "CC_SCK") (class "Default")
      (node (ref "STMF401") (pin "53") (pinfunction "PC12_53") (pintype "bidirectional"))
      (node (ref "U$4") (pin "28") (pinfunction "SCLK_28") (pintype "input"))
    )
    (net (code "23") (name "CH1_A") (class "Default")
      (node (ref "JP1") (pin "1") (pinfunction "1_1") (pintype "passive"))
      (node (ref "OK2") (pin "8") (pinfunction "COL_8") (pintype "passive"))
    )
    (net (code "24") (name "CH1_B") (class "Default")
      (node (ref "JP1") (pin "2") (pinfunction "2_2") (pintype "passive"))
      (node (ref "OK2") (pin "7") (pinfunction "EMIT_7") (pintype "passive"))
    )
    (net (code "25") (name "CH1_IN") (class "Default")
      (node (ref "IC5") (pin "15") (pinfunction "QA_15") (pintype "tri_state"))
      (node (ref "OK2") (pin "2") (pinfunction "C_2") (pintype "passive"))
    )
    (net (code "26") (name "CH2_A") (class "Default")
      (node (ref "JP1") (pin "3") (pinfunction "3_3") (pintype "passive"))
      (node (ref "OK2") (pin "6") (pinfunction "COL_6") (pintype "passive"))
    )
    (net (code "27") (name "CH2_B") (class "Default")
      (node (ref "JP1") (pin "4") (pinfunction "4_4") (pintype "passive"))
      (node (ref "OK2") (pin "5") (pinfunction "EMIT_5") (pintype "passive"))
    )
    (net (code "28") (name "CH2_IN") (class "Default")
      (node (ref "IC5") (pin "1") (pinfunction "QB_1") (pintype "tri_state"))
      (node (ref "OK2") (pin "4") (pinfunction "C_4") (pintype "passive"))
    )
    (net (code "29") (name "CH3_A") (class "Default")
      (node (ref "JP1") (pin "5") (pinfunction "5_5") (pintype "passive"))
      (node (ref "OK1") (pin "8") (pinfunction "COL_8") (pintype "passive"))
    )
    (net (code "30") (name "CH3_B") (class "Default")
      (node (ref "JP1") (pin "6") (pinfunction "6_6") (pintype "passive"))
      (node (ref "OK1") (pin "7") (pinfunction "EMIT_7") (pintype "passive"))
    )
    (net (code "31") (name "CH3_IN") (class "Default")
      (node (ref "IC5") (pin "2") (pinfunction "QC_2") (pintype "tri_state"))
      (node (ref "OK1") (pin "2") (pinfunction "C_2") (pintype "passive"))
    )
    (net (code "32") (name "CH4_A") (class "Default")
      (node (ref "JP1") (pin "7") (pinfunction "7_7") (pintype "passive"))
      (node (ref "OK1") (pin "6") (pinfunction "COL_6") (pintype "passive"))
    )
    (net (code "33") (name "CH4_B") (class "Default")
      (node (ref "JP1") (pin "8") (pinfunction "8_8") (pintype "passive"))
      (node (ref "OK1") (pin "5") (pinfunction "EMIT_5") (pintype "passive"))
    )
    (net (code "34") (name "CH4_IN") (class "Default")
      (node (ref "IC5") (pin "3") (pinfunction "QD_3") (pintype "tri_state"))
      (node (ref "OK1") (pin "4") (pinfunction "C_4") (pintype "passive"))
    )
    (net (code "35") (name "DC_VOUT") (class "Default")
      (node (ref "DCDC") (pin "VOUT") (pinfunction "VOUT_VOUT") (pintype "bidirectional"))
      (node (ref "PWR") (pin "2") (pinfunction "2_2") (pintype "passive"))
    )
    (net (code "36") (name "DGND") (class "Default")
      (node (ref "ADE-C5") (pin "-") (pinfunction "-_-") (pintype "passive"))
      (node (ref "ANT1") (pin "P$1") (pinfunction "GND_P$1") (pintype "bidirectional"))
      (node (ref "ANT1") (pin "P$2") (pinfunction "GND_P$2") (pintype "bidirectional"))
      (node (ref "ANT2") (pin "P$1") (pinfunction "GND_P$1") (pintype "bidirectional"))
      (node (ref "ANT2") (pin "P$2") (pinfunction "GND_P$2") (pintype "bidirectional"))
      (node (ref "B1") (pin "2") (pinfunction "GND_2") (pintype "bidirectional"))
      (node (ref "B1") (pin "5") (pinfunction "GND_5") (pintype "bidirectional"))
      (node (ref "B1") (pin "6") (pinfunction "GND_6") (pintype "bidirectional"))
      (node (ref "BAT1") (pin "GND") (pinfunction "-_GND") (pintype "power_in"))
      (node (ref "C10") (pin "2") (pinfunction "2_2") (pintype "passive"))
      (node (ref "C20") (pin "2") (pinfunction "2_2") (pintype "passive"))
      (node (ref "C21") (pin "1") (pinfunction "1_1") (pintype "passive"))
      (node (ref "C22") (pin "1") (pinfunction "1_1") (pintype "passive"))
      (node (ref "C23") (pin "1") (pinfunction "1_1") (pintype "passive"))
      (node (ref "C24") (pin "2") (pinfunction "2_2") (pintype "passive"))
      (node (ref "C26") (pin "2") (pinfunction "2_2") (pintype "passive"))
      (node (ref "C27") (pin "2") (pinfunction "2_2") (pintype "passive"))
      (node (ref "C28") (pin "2") (pinfunction "2_2") (pintype "passive"))
      (node (ref "C30") (pin "1") (pinfunction "1_1") (pintype "passive"))
      (node (ref "C31") (pin "2") (pinfunction "2_2") (pintype "passive"))
      (node (ref "C33") (pin "2") (pinfunction "2_2") (pintype "passive"))
      (node (ref "C35") (pin "2") (pinfunction "2_2") (pintype "passive"))
      (node (ref "C36") (pin "1") (pinfunction "1_1") (pintype "passive"))
      (node (ref "C37") (pin "-") (pinfunction "-_-") (pintype "passive"))
      (node (ref "C40") (pin "2") (pinfunction "2_2") (pintype "passive"))
      (node (ref "C41") (pin "2") (pinfunction "2_2") (pintype "passive"))
      (node (ref "C43") (pin "2") (pinfunction "2_2") (pintype "passive"))
      (node (ref "C44") (pin "2") (pinfunction "2_2") (pintype "passive"))
      (node (ref "C45") (pin "2") (pinfunction "2_2") (pintype "passive"))
      (node (ref "C46") (pin "2") (pinfunction "2_2") (pintype "passive"))
      (node (ref "C50") (pin "2") (pinfunction "2_2") (pintype "passive"))
      (node (ref "C51") (pin "2") (pinfunction "2_2") (pintype "passive"))
      (node (ref "C52") (pin "2") (pinfunction "2_2") (pintype "passive"))
      (node (ref "C53") (pin "2") (pinfunction "2_2") (pintype "passive"))
      (node (ref "C54") (pin "2") (pinfunction "2_2") (pintype "passive"))
      (node (ref "C55") (pin "2") (pinfunction "2_2") (pintype "passive"))
      (node (ref "C56") (pin "2") (pinfunction "2_2") (pintype "passive"))
      (node (ref "C57") (pin "2") (pinfunction "2_2") (pintype "passive"))
      (node (ref "C70") (pin "2") (pinfunction "2_2") (pintype "passive"))
      (node (ref "C73") (pin "2") (pinfunction "2_2") (pintype "passive"))
      (node (ref "C74") (pin "2") (pinfunction "2_2") (pintype "passive"))
      (node (ref "C80") (pin "1") (pinfunction "1_1") (pintype "passive"))
      (node (ref "C81") (pin "1") (pinfunction "1_1") (pintype "passive"))
      (node (ref "C96") (pin "-") (pinfunction "-_-") (pintype "passive"))
      (node (ref "C97") (pin "-") (pinfunction "-_-") (pintype "passive"))
      (node (ref "DCDC") (pin "GND$1") (pinfunction "GNDI_GND$1") (pintype "bidirectional"))
      (node (ref "DCDC") (pin "GND$2") (pinfunction "GNDO_GND$2") (pintype "bidirectional"))
      (node (ref "ESP") (pin "GND") (pinfunction "GND_GND") (pintype "bidirectional"))
      (node (ref "ESP") (pin "GPIO15") (pinfunction "GPIO15_GPIO15") (pintype "bidirectional"))
      (node (ref "ESP-C1") (pin "2") (pinfunction "2_2") (pintype "passive"))
      (node (ref "ESP-GPIO0") (pin "3") (pinfunction "3_3") (pintype "passive"))
      (node (ref "HLK-PM01") (pin "GND") (pinfunction "GND_GND") (pintype "bidirectional"))
      (node (ref "IC1") (pin "P$17") (pinfunction "GND_P$17") (pintype "power_in"))
      (node (ref "IC1") (pin "P$18") (pinfunction "GND_P$18") (pintype "power_in"))
      (node (ref "IC1") (pin "P$29") (pinfunction "GND_P$29") (pintype "power_in"))
      (node (ref "IC1") (pin "P$39") (pinfunction "GND_P$39") (pintype "power_in"))
      (node (ref "IC1") (pin "P$45") (pinfunction "GND_P$45") (pintype "power_in"))
      (node (ref "IC1") (pin "P$46") (pinfunction "GND_P$46") (pintype "power_in"))
      (node (ref "IC1") (pin "P$53") (pinfunction "GND_P$53") (pintype "power_in"))
      (node (ref "IC1") (pin "P$54") (pinfunction "GND_P$54") (pintype "power_in"))
      (node (ref "IC1") (pin "P$58") (pinfunction "GND_P$58") (pintype "power_in"))
      (node (ref "IC1") (pin "P$59") (pinfunction "GND_P$59") (pintype "power_in"))
      (node (ref "IC1") (pin "P$61") (pinfunction "GND_P$61") (pintype "power_in"))
      (node (ref "IC1") (pin "P$62") (pinfunction "GND_P$62") (pintype "power_in"))
      (node (ref "IC1") (pin "P$63") (pinfunction "GND_P$63") (pintype "power_in"))
      (node (ref "IC1") (pin "P$64") (pinfunction "GND_P$64") (pintype "power_in"))
      (node (ref "IC1") (pin "P$65") (pinfunction "GND_P$65") (pintype "power_in"))
      (node (ref "IC2") (pin "13") (pinfunction "G_13") (pintype "input"))
      (node (ref "IC2") (pin "8") (pinfunction "GND_8") (pintype "power_in"))
      (node (ref "IC3") (pin "13") (pinfunction "G_13") (pintype "input"))
      (node (ref "IC3") (pin "8") (pinfunction "GND_8") (pintype "power_in"))
      (node (ref "IC4") (pin "2") (pinfunction "DGND_2") (pintype "power_in"))
      (node (ref "IC4") (pin "21") (pinfunction "CS_21") (pintype "input"))
      (node (ref "IC5") (pin "13") (pinfunction "G_13") (pintype "input"))
      (node (ref "IC5") (pin "8") (pinfunction "GND_8") (pintype "power_in"))
      (node (ref "L1") (pin "2") (pinfunction "2_2") (pintype "passive"))
      (node (ref "LCD14") (pin "LCD_GND") (pinfunction "LCD_GND_LCD_GND") (pintype "power_in"))
      (node (ref "LCD14") (pin "T_CS") (pinfunction "T_CS_T_CS") (pintype "bidirectional"))
      (node (ref "LCD_C1") (pin "2") (pinfunction "2_2") (pintype "passive"))
      (node (ref "MQ2-R1") (pin "1") (pinfunction "1_1") (pintype "passive"))
      (node (ref "R31") (pin "1") (pinfunction "1_1") (pintype "passive"))
      (node (ref "R50") (pin "1") (pinfunction "1_1") (pintype "passive"))
      (node (ref "R52") (pin "5") (pinfunction "2_5") (pintype "passive"))
      (node (ref "R52") (pin "6") (pinfunction "2_6") (pintype "passive"))
      (node (ref "R52") (pin "7") (pinfunction "2_7") (pintype "passive"))
      (node (ref "R52") (pin "8") (pinfunction "2_8") (pintype "passive"))
      (node (ref "R53") (pin "1") (pinfunction "1_1") (pintype "passive"))
      (node (ref "R90") (pin "2") (pinfunction "2_2") (pintype "passive"))
      (node (ref "R96") (pin "2") (pinfunction "2_2") (pintype "passive"))
      (node (ref "RBIAS") (pin "2") (pinfunction "2_2") (pintype "passive"))
      (node (ref "RJ-1") (pin "SHIELD$1") (pinfunction "P$5_SHIELD$1") (pintype "bidirectional"))
      (node (ref "RJ-2") (pin "SHIELD$1") (pinfunction "P$5_SHIELD$1") (pintype "bidirectional"))
      (node (ref "RJ-3") (pin "SHIELD$1") (pinfunction "P$5_SHIELD$1") (pintype "bidirectional"))
      (node (ref "S1") (pin "3") (pinfunction "3_3") (pintype "passive"))
      (node (ref "S1") (pin "4") (pinfunction "4_4") (pintype "passive"))
      (node (ref "SENSOR-MQ2") (pin "HB") (pinfunction "HB_HB") (pintype "bidirectional"))
      (node (ref "SIM900-C3") (pin "2") (pinfunction "2_2") (pintype "passive"))
      (node (ref "SIM900-C4") (pin "2") (pinfunction "2_2") (pintype "passive"))
      (node (ref "SIM900-C5") (pin "2") (pinfunction "2_2") (pintype "passive"))
      (node (ref "SIMHOLDER") (pin "SHIELD_GND$1") (pinfunction "GND$1_SHIELD_GND$1") (pintype "bidirectional"))
      (node (ref "SIMHOLDER") (pin "SHIELD_GND$2") (pinfunction "GND$2_SHIELD_GND$2") (pintype "bidirectional"))
      (node (ref "SIMHOLDER") (pin "SIM_GND") (pinfunction "SIM_GND_SIM_GND") (pintype "bidirectional"))
      (node (ref "SR_OUT1") (pin "2") (pinfunction "2_2") (pintype "passive"))
      (node (ref "SR_OUT2") (pin "2") (pinfunction "2_2") (pintype "passive"))
      (node (ref "STM-C13") (pin "2") (pinfunction "2_2") (pintype "passive"))
      (node (ref "STM-SWD") (pin "3") (pinfunction "3_3") (pintype "passive"))
      (node (ref "STM-USART") (pin "4") (pinfunction "4_4") (pintype "passive"))
      (node (ref "STMF401") (pin "18") (pinfunction "VSS_4_18") (pintype "power_in"))
      (node (ref "STMF401") (pin "31") (pinfunction "VSS_1_31") (pintype "power_in"))
      (node (ref "STMF401") (pin "47") (pinfunction "VSS_2_47") (pintype "power_in"))
      (node (ref "STMF401") (pin "63") (pinfunction "VSS_3_63") (pintype "power_in"))
      (node (ref "SYS-C1") (pin "2") (pinfunction "2_2") (pintype "passive"))
      (node (ref "T1") (pin "E") (pinfunction "E_E") (pintype "passive"))
      (node (ref "T2") (pin "E") (pinfunction "E_E") (pintype "passive"))
      (node (ref "T3") (pin "E") (pinfunction "E_E") (pintype "passive"))
      (node (ref "U$17") (pin "GND") (pinfunction "GND_GND") (pintype "bidirectional"))
      (node (ref "U$4") (pin "3") (pinfunction "CS_3") (pintype "input"))
      (node (ref "U2") (pin "14") (pinfunction "AGND_14") (pintype "passive"))
      (node (ref "U2") (pin "16") (pinfunction "AGND_16") (pintype "passive"))
      (node (ref "U2") (pin "19") (pinfunction "AGND_19") (pintype "passive"))
      (node (ref "U2") (pin "29") (pinfunction "GND_29") (pintype "passive"))
      (node (ref "U2") (pin "3") (pinfunction "AGND_3") (pintype "passive"))
      (node (ref "U2") (pin "48") (pinfunction "AGND_48") (pintype "passive"))
      (node (ref "U2") (pin "9") (pinfunction "AGND_9") (pintype "passive"))
      (node (ref "USB_IN") (pin "GND1") (pinfunction "GND_GND1") (pintype "bidirectional"))
      (node (ref "USB_IN") (pin "SHIELD1") (pinfunction "SHIELD_SHIELD1") (pintype "bidirectional"))
      (node (ref "USB_IN") (pin "SHIELD2") (pinfunction "SHIELD_SHIELD2") (pintype "bidirectional"))
      (node (ref "USB_IN") (pin "SHIELD3") (pinfunction "SHIELD_SHIELD3") (pintype "bidirectional"))
      (node (ref "W5500-C13") (pin "-") (pinfunction "-_-") (pintype "passive"))
    )
    (net (code "37") (name "DHT_DATA") (class "Default")
      (node (ref "DHT-R1") (pin "2") (pinfunction "2_2") (pintype "passive"))
      (node (ref "STMF401") (pin "54") (pinfunction "PD2_54") (pintype "bidirectional"))
      (node (ref "U$17") (pin "DATA") (pinfunction "DATA_DATA") (pintype "bidirectional"))
    )
    (net (code "38") (name "ESP_GPIO0") (class "Default")
      (node (ref "ESP") (pin "GPIO00") (pinfunction "GPIO0_GPIO00") (pintype "bidirectional"))
      (node (ref "ESP-GPIO0") (pin "2") (pinfunction "2_2") (pintype "passive"))
    )
    (net (code "39") (name "ESP_RX") (class "Default")
      (node (ref "ESP") (pin "RXD") (pinfunction "RXD_RXD") (pintype "bidirectional"))
      (node (ref "ESP_EXT") (pin "3") (pinfunction "3_3") (pintype "passive"))
      (node (ref "JRX") (pin "1") (pinfunction "1_1") (pintype "passive"))
    )
    (net (code "40") (name "ESP_TX") (class "Default")
      (node (ref "ESP") (pin "TXD") (pinfunction "TXD_TXD") (pintype "bidirectional"))
      (node (ref "ESP_EXT") (pin "4") (pinfunction "4_4") (pintype "passive"))
      (node (ref "JTX") (pin "1") (pinfunction "1_1") (pintype "passive"))
    )
    (net (code "41") (name "ETH_CS") (class "Default")
      (node (ref "R54") (pin "1") (pinfunction "1_1") (pintype "passive"))
      (node (ref "STMF401") (pin "33") (pinfunction "PB12_33") (pintype "bidirectional"))
      (node (ref "U2") (pin "32") (pinfunction "SCS_N_32") (pintype "passive"))
    )
    (net (code "42") (name "ETH_MISO") (class "Default")
      (node (ref "STMF401") (pin "35") (pinfunction "PB14_35") (pintype "bidirectional"))
      (node (ref "U2") (pin "34") (pinfunction "MISO_34") (pintype "passive"))
    )
    (net (code "43") (name "ETH_MOSI") (class "Default")
      (node (ref "STMF401") (pin "36") (pinfunction "PB15_36") (pintype "bidirectional"))
      (node (ref "U2") (pin "35") (pinfunction "MOSI_35") (pintype "passive"))
    )
    (net (code "44") (name "ETH_RSTN") (class "Default")
      (node (ref "R51") (pin "2") (pinfunction "2_2") (pintype "passive"))
      (node (ref "STMF401") (pin "37") (pinfunction "PC6_37") (pintype "bidirectional"))
      (node (ref "U2") (pin "37") (pinfunction "RST_N_37") (pintype "passive"))
    )
    (net (code "45") (name "ETH_SCK") (class "Default")
      (node (ref "STMF401") (pin "34") (pinfunction "PB13_34") (pintype "bidirectional"))
      (node (ref "U2") (pin "33") (pinfunction "SCLK_33") (pintype "passive"))
    )
    (net (code "46") (name "LCD_CS") (class "Default")
      (node (ref "LCD14") (pin "LCD_CS") (pinfunction "LCD_CS_LCD_CS") (pintype "bidirectional"))
      (node (ref "STMF401") (pin "20") (pinfunction "PA4_20") (pintype "bidirectional"))
    )
    (net (code "47") (name "LCD_D{slash}C") (class "Default")
      (node (ref "LCD14") (pin "LCD_D/C") (pinfunction "LCD_D/C_LCD_D/C") (pintype "bidirectional"))
      (node (ref "STMF401") (pin "24") (pinfunction "PC4_24") (pintype "bidirectional"))
    )
    (net (code "48") (name "LCD_LED") (class "Default")
      (node (ref "LCD-R1") (pin "1") (pinfunction "1_1") (pintype "passive"))
      (node (ref "LCD14") (pin "LED") (pinfunction "LCD_LED_LED") (pintype "bidirectional"))
    )
    (net (code "49") (name "LCD_MISO") (class "Default")
      (node (ref "LCD14") (pin "LCD_MISO") (pinfunction "LCD_MISO_LCD_MISO") (pintype "bidirectional"))
      (node (ref "LCD14") (pin "SD_MISO") (pinfunction "SD_MISO_SD_MISO") (pintype "bidirectional"))
      (node (ref "STMF401") (pin "22") (pinfunction "PA6_22") (pintype "bidirectional"))
    )
    (net (code "50") (name "LCD_MOSI") (class "Default")
      (node (ref "LCD14") (pin "LCD_MOSI") (pinfunction "LCD_MOSI_LCD_MOSI") (pintype "bidirectional"))
      (node (ref "LCD14") (pin "SD_MOSI") (pinfunction "SD_MOSI_SD_MOSI") (pintype "bidirectional"))
      (node (ref "STMF401") (pin "23") (pinfunction "PA7_23") (pintype "bidirectional"))
    )
    (net (code "51") (name "LCD_RESET") (class "Default")
      (node (ref "LCD14") (pin "LCD_RESET") (pinfunction "LCD_RESET_LCD_RESET") (pintype "bidirectional"))
      (node (ref "STMF401") (pin "25") (pinfunction "PC5_25") (pintype "bidirectional"))
    )
    (net (code "52") (name "LCD_SCK") (class "Default")
      (node (ref "LCD14") (pin "LCD_SCK") (pinfunction "LCD_SCK_LCD_SCK") (pintype "bidirectional"))
      (node (ref "LCD14") (pin "SD_SCK") (pinfunction "SD_SCK_SD_SCK") (pintype "bidirectional"))
      (node (ref "STMF401") (pin "21") (pinfunction "PA5_21") (pintype "bidirectional"))
    )
    (net (code "53") (name "LINKLED") (class "Default")
      (node (ref "ETH-R5") (pin "1") (pinfunction "1_1") (pintype "passive"))
      (node (ref "U2") (pin "25") (pinfunction "LINKLED_25") (pintype "passive"))
    )
    (net (code "54") (name "MQ2_DATA") (class "Default")
      (node (ref "MQ2-R1") (pin "2") (pinfunction "2_2") (pintype "passive"))
      (node (ref "SENSOR-MQ2") (pin "B1") (pinfunction "B1_B1") (pintype "bidirectional"))
      (node (ref "SENSOR-MQ2") (pin "B2") (pinfunction "B2_B2") (pintype "bidirectional"))
      (node (ref "STMF401") (pin "6") (pinfunction "PH1-_OSC_OUT_6") (pintype "bidirectional"))
    )
    (net (code "55") (name "N") (class "Default")
      (node (ref "HLK-PM01") (pin "AC$2") (pinfunction "AC_IN$2_AC$2") (pintype "bidirectional"))
      (node (ref "TERM_BLOCK") (pin "PIN$4") (pinfunction "P$4_PIN$4") (pintype "bidirectional"))
      (node (ref "TV16-1") (pin "IB") (pinfunction "IB_IB") (pintype "bidirectional"))
      (node (ref "TV16-2") (pin "IB") (pinfunction "IB_IB") (pintype "bidirectional"))
      (node (ref "TV16-3") (pin "IB") (pinfunction "IB_IB") (pintype "bidirectional"))
    )
    (net (code "56") (name "Net-(ADE-R1-Pad1)") (class "Default")
      (node (ref "ADE-R1") (pin "1") (pinfunction "1_1") (pintype "passive"))
      (node (ref "RTO1") (pin "2") (pinfunction "2_2") (pintype "passive"))
      (node (ref "TV16-1") (pin "OA") (pinfunction "OA_OA") (pintype "bidirectional"))
    )
    (net (code "57") (name "Net-(ADE-R2-Pad1)") (class "Default")
      (node (ref "ADE-R2") (pin "1") (pinfunction "1_1") (pintype "passive"))
      (node (ref "RTO2") (pin "2") (pinfunction "2_2") (pintype "passive"))
      (node (ref "TV16-2") (pin "OA") (pinfunction "OA_OA") (pintype "bidirectional"))
    )
    (net (code "58") (name "Net-(ADE-R3-Pad1)") (class "Default")
      (node (ref "ADE-R3") (pin "1") (pinfunction "1_1") (pintype "passive"))
      (node (ref "RTO3") (pin "2") (pinfunction "2_2") (pintype "passive"))
      (node (ref "TV16-3") (pin "OA") (pinfunction "OA_OA") (pintype "bidirectional"))
    )
    (net (code "59") (name "Net-(ADE-R7-Pad1)") (class "Default")
      (node (ref "ADE-R7") (pin "1") (pinfunction "1_1") (pintype "passive"))
      (node (ref "RTO1") (pin "1") (pinfunction "1_1") (pintype "passive"))
      (node (ref "RTO2") (pin "1") (pinfunction "1_1") (pintype "passive"))
      (node (ref "RTO3") (pin "1") (pinfunction "1_1") (pintype "passive"))
      (node (ref "TV16-1") (pin "OB") (pinfunction "OB_OB") (pintype "bidirectional"))
      (node (ref "TV16-2") (pin "OB") (pinfunction "OB_OB") (pintype "bidirectional"))
      (node (ref "TV16-3") (pin "OB") (pinfunction "OB_OB") (pintype "bidirectional"))
    )
    (net (code "60") (name "Net-(ADE-R8-Pad2)") (class "Default")
      (node (ref "ADE-R8") (pin "2") (pinfunction "2_2") (pintype "passive"))
      (node (ref "ADE-R9") (pin "1") (pinfunction "1_1") (pintype "passive"))
      (node (ref "RJ-3") (pin "P$3") (pinfunction "P$3_P$3") (pintype "bidirectional"))
      (node (ref "RJ-3") (pin "P$4") (pinfunction "P$4_P$4") (pintype "bidirectional"))
    )
    (net (code "61") (name "Net-(ADE-R10-Pad1)") (class "Default")
      (node (ref "ADE-R10") (pin "1") (pinfunction "1_1") (pintype "passive"))
      (node (ref "ADE-R8") (pin "1") (pinfunction "1_1") (pintype "passive"))
      (node (ref "RJ-3") (pin "P$1") (pinfunction "P$1_P$1") (pintype "bidirectional"))
      (node (ref "RJ-3") (pin "P$2") (pinfunction "P$2_P$2") (pintype "bidirectional"))
    )
    (net (code "62") (name "Net-(ADE-R11-Pad1)") (class "Default")
      (node (ref "ADE-R11") (pin "1") (pinfunction "1_1") (pintype "passive"))
      (node (ref "ADE-R13") (pin "1") (pinfunction "1_1") (pintype "passive"))
      (node (ref "RJ-2") (pin "P$1") (pinfunction "P$1_P$1") (pintype "bidirectional"))
      (node (ref "RJ-2") (pin "P$2") (pinfunction "P$2_P$2") (pintype "bidirectional"))
    )
    (net (code "63") (name "Net-(ADE-R11-Pad2)") (class "Default")
      (node (ref "ADE-R11") (pin "2") (pinfunction "2_2") (pintype "passive"))
      (node (ref "ADE-R12") (pin "1") (pinfunction "1_1") (pintype "passive"))
      (node (ref "RJ-2") (pin "P$3") (pinfunction "P$3_P$3") (pintype "bidirectional"))
      (node (ref "RJ-2") (pin "P$4") (pinfunction "P$4_P$4") (pintype "bidirectional"))
    )
    (net (code "64") (name "Net-(ADE-R14-Pad1)") (class "Default")
      (node (ref "ADE-R14") (pin "1") (pinfunction "1_1") (pintype "passive"))
      (node (ref "ADE-R16") (pin "1") (pinfunction "1_1") (pintype "passive"))
      (node (ref "RJ-1") (pin "P$1") (pinfunction "P$1_P$1") (pintype "bidirectional"))
      (node (ref "RJ-1") (pin "P$2") (pinfunction "P$2_P$2") (pintype "bidirectional"))
    )
    (net (code "65") (name "Net-(ADE-R14-Pad2)") (class "Default")
      (node (ref "ADE-R14") (pin "2") (pinfunction "2_2") (pintype "passive"))
      (node (ref "ADE-R15") (pin "1") (pinfunction "1_1") (pintype "passive"))
      (node (ref "RJ-1") (pin "P$3") (pinfunction "P$3_P$3") (pintype "bidirectional"))
      (node (ref "RJ-1") (pin "P$4") (pinfunction "P$4_P$4") (pintype "bidirectional"))
    )
    (net (code "66") (name "Net-(ANT1-SIGNAL)") (class "Default")
      (node (ref "ANT1") (pin "P$3") (pinfunction "SIGNAL_P$3") (pintype "bidirectional"))
      (node (ref "IC1") (pin "P$60") (pinfunction "RF_ANT_P$60") (pintype "bidirectional"))
    )
    (net (code "67") (name "Net-(ANT2-SIGNAL)") (class "Default")
      (node (ref "ANT2") (pin "P$3") (pinfunction "SIGNAL_P$3") (pintype "bidirectional"))
      (node (ref "B1") (pin "1") (pinfunction "ANT_1") (pintype "bidirectional"))
    )
    (net (code "68") (name "Net-(B1-BAL_N)") (class "Default")
      (node (ref "B1") (pin "3") (pinfunction "BAL_N_3") (pintype "bidirectional"))
      (node (ref "U$4") (pin "19") (pinfunction "RF-N_19") (pintype "bidirectional"))
    )
    (net (code "69") (name "Net-(B1-BAL_P)") (class "Default")
      (node (ref "B1") (pin "4") (pinfunction "BAL_P_4") (pintype "bidirectional"))
      (node (ref "U$4") (pin "17") (pinfunction "RF-P_17") (pintype "bidirectional"))
    )
    (net (code "70") (name "Net-(ETHERNET-LED1_K)") (class "Default")
      (node (ref "ETH-R4") (pin "2") (pinfunction "2_2") (pintype "passive"))
      (node (ref "ETHERNET") (pin "10") (pinfunction "LED1_K_10") (pintype "bidirectional"))
    )
    (net (code "71") (name "Net-(ETHERNET-LED2_K)") (class "Default")
      (node (ref "ETH-R5") (pin "2") (pinfunction "2_2") (pintype "passive"))
      (node (ref "ETHERNET") (pin "11") (pinfunction "LED2_K_11") (pintype "bidirectional"))
    )
    (net (code "72") (name "Net-(ETHERNET-RCT)") (class "Default")
      (node (ref "C30") (pin "2") (pinfunction "2_2") (pintype "passive"))
      (node (ref "ETHERNET") (pin "6") (pinfunction "RCT_6") (pintype "bidirectional"))
      (node (ref "R30") (pin "1") (pinfunction "1_1") (pintype "passive"))
      (node (ref "R32") (pin "2") (pinfunction "2_2") (pintype "passive"))
    )
    (net (code "73") (name "Net-(ETHERNET-RX+)") (class "Default")
      (node (ref "C32") (pin "1") (pinfunction "1_1") (pintype "passive"))
      (node (ref "ETHERNET") (pin "7") (pinfunction "RX+_7") (pintype "bidirectional"))
    )
    (net (code "74") (name "Net-(ETHERNET-RX-)") (class "Default")
      (node (ref "C34") (pin "1") (pinfunction "1_1") (pintype "passive"))
      (node (ref "ETHERNET") (pin "8") (pinfunction "RX-_8") (pintype "bidirectional"))
    )
    (net (code "75") (name "Net-(ETHERNET-TCT)") (class "Default")
      (node (ref "C36") (pin "2") (pinfunction "2_2") (pintype "passive"))
      (node (ref "ETHERNET") (pin "3") (pinfunction "TCT_3") (pintype "bidirectional"))
      (node (ref "R33") (pin "1") (pinfunction "1_1") (pintype "passive"))
    )
    (net (code "76") (name "Net-(IC1-SIM_CLK)") (class "Default")
      (node (ref "IC1") (pin "P$32") (pinfunction "SIM_CLK_P$32") (pintype "bidirectional"))
      (node (ref "SIM900-R2") (pin "1") (pinfunction "1_1") (pintype "passive"))
    )
    (net (code "77") (name "Net-(IC1-SIM_DATA)") (class "Default")
      (node (ref "IC1") (pin "P$31") (pinfunction "SIM_DATA_P$31") (pintype "bidirectional"))
      (node (ref "SIM900-R3") (pin "1") (pinfunction "1_1") (pintype "passive"))
    )
    (net (code "78") (name "Net-(IC1-SIM_RST)") (class "Default")
      (node (ref "IC1") (pin "P$33") (pinfunction "SIM_RST_P$33") (pintype "bidirectional"))
      (node (ref "SIM900-R1") (pin "1") (pinfunction "1_1") (pintype "passive"))
    )
    (net (code "79") (name "Net-(IC1-VBAT1)") (class "Default")
      (node (ref "C96") (pin "+") (pinfunction "+_+") (pintype "passive"))
      (node (ref "C97") (pin "+") (pinfunction "+_+") (pintype "passive"))
      (node (ref "IC1") (pin "P$55") (pinfunction "VBAT1_P$55") (pintype "power_in"))
      (node (ref "IC1") (pin "P$56") (pinfunction "VBAT2_P$56") (pintype "power_in"))
      (node (ref "IC1") (pin "P$57") (pinfunction "VBAT3_P$57") (pintype "power_in"))
      (node (ref "L2") (pin "1") (pinfunction "1_1") (pintype "passive"))
    )
    (net (code "80") (name "Net-(IC1-VRTC)") (class "Default")
      (node (ref "IC1") (pin "P$26") (pinfunction "VRTC_P$26") (pintype "power_in"))
      (node (ref "SIM900-C3") (pin "1") (pinfunction "1_1") (pintype "passive"))
    )
    (net (code "81") (name "Net-(IC4A-CLKIN)") (class "Default")
      (node (ref "ADE-XTAL") (pin "1") (pinfunction "1_1") (pintype "passive"))
      (node (ref "C73") (pin "1") (pinfunction "1_1") (pintype "passive"))
      (node (ref "IC4") (pin "19") (pinfunction "CLKIN_19") (pintype "input"))
    )
    (net (code "82") (name "Net-(IC4A-CLKOUT)") (class "Default")
      (node (ref "ADE-XTAL") (pin "2") (pinfunction "2_2") (pintype "passive"))
      (node (ref "C74") (pin "1") (pinfunction "1_1") (pintype "passive"))
      (node (ref "IC4") (pin "20") (pinfunction "CLKOUT_20") (pintype "output"))
    )
    (net (code "83") (name "Net-(IC4C-IN)") (class "Default")
      (node (ref "ADE-C12") (pin "1") (pinfunction "1_1") (pintype "passive"))
      (node (ref "ADE-R10") (pin "2") (pinfunction "2_2") (pintype "passive"))
      (node (ref "IC4") (pin "6") (pinfunction "IN_6") (pintype "input"))
    )
    (net (code "84") (name "Net-(IC4C-IP)") (class "Default")
      (node (ref "ADE-C11") (pin "1") (pinfunction "1_1") (pintype "passive"))
      (node (ref "ADE-R9") (pin "2") (pinfunction "2_2") (pintype "passive"))
      (node (ref "IC4") (pin "5") (pinfunction "IP_5") (pintype "input"))
    )
    (net (code "85") (name "Net-(IC4D-IN)") (class "Default")
      (node (ref "ADE-C14") (pin "1") (pinfunction "1_1") (pintype "passive"))
      (node (ref "ADE-R13") (pin "2") (pinfunction "2_2") (pintype "passive"))
      (node (ref "IC4") (pin "8") (pinfunction "IN_8") (pintype "input"))
    )
    (net (code "86") (name "Net-(IC4D-IP)") (class "Default")
      (node (ref "ADE-C13") (pin "1") (pinfunction "1_1") (pintype "passive"))
      (node (ref "ADE-R12") (pin "2") (pinfunction "2_2") (pintype "passive"))
      (node (ref "IC4") (pin "7") (pinfunction "IP_7") (pintype "input"))
    )
    (net (code "87") (name "Net-(IC4E-IN)") (class "Default")
      (node (ref "ADE-C16") (pin "1") (pinfunction "1_1") (pintype "passive"))
      (node (ref "ADE-R16") (pin "2") (pinfunction "2_2") (pintype "passive"))
      (node (ref "IC4") (pin "10") (pinfunction "IN_10") (pintype "input"))
    )
    (net (code "88") (name "Net-(IC4E-IP)") (class "Default")
      (node (ref "ADE-C15") (pin "1") (pinfunction "1_1") (pintype "passive"))
      (node (ref "ADE-R15") (pin "2") (pinfunction "2_2") (pintype "passive"))
      (node (ref "IC4") (pin "9") (pinfunction "IP_9") (pintype "input"))
    )
    (net (code "89") (name "Net-(IC4F-REF)") (class "Default")
      (node (ref "C71") (pin "1") (pinfunction "1_1") (pintype "passive"))
      (node (ref "C72") (pin "1") (pinfunction "1_1") (pintype "passive"))
      (node (ref "IC4") (pin "12") (pinfunction "REF_12") (pintype "bidirectional"))
    )
    (net (code "90") (name "Net-(IC4G-VAP)") (class "Default")
      (node (ref "ADE-C7") (pin "1") (pinfunction "1_1") (pintype "passive"))
      (node (ref "ADE-R1") (pin "2") (pinfunction "2_2") (pintype "passive"))
      (node (ref "ADE-R4") (pin "2") (pinfunction "2_2") (pintype "passive"))
      (node (ref "IC4") (pin "16") (pinfunction "VAP_16") (pintype "input"))
    )
    (net (code "91") (name "Net-(IC4G-VBP)") (class "Default")
      (node (ref "ADE-C8") (pin "1") (pinfunction "1_1") (pintype "passive"))
      (node (ref "ADE-R2") (pin "2") (pinfunction "2_2") (pintype "passive"))
      (node (ref "ADE-R5") (pin "2") (pinfunction "2_2") (pintype "passive"))
      (node (ref "IC4") (pin "15") (pinfunction "VBP_15") (pintype "input"))
    )
    (net (code "92") (name "Net-(IC4G-VCP)") (class "Default")
      (node (ref "ADE-C9") (pin "1") (pinfunction "1_1") (pintype "passive"))
      (node (ref "ADE-R3") (pin "2") (pinfunction "2_2") (pintype "passive"))
      (node (ref "ADE-R6") (pin "2") (pinfunction "2_2") (pintype "passive"))
      (node (ref "IC4") (pin "14") (pinfunction "VCP_14") (pintype "input"))
    )
    (net (code "93") (name "Net-(IC4G-VN)") (class "Default")
      (node (ref "ADE-C10") (pin "1") (pinfunction "1_1") (pintype "passive"))
      (node (ref "ADE-R7") (pin "2") (pinfunction "2_2") (pintype "passive"))
      (node (ref "IC4") (pin "13") (pinfunction "VN_13") (pintype "input"))
    )
    (net (code "94") (name "Net-(LED1-PadA)") (class "Default")
      (node (ref "LED1") (pin "A") (pinfunction "A_A") (pintype "passive"))
      (node (ref "R94") (pin "1") (pinfunction "1_1") (pintype "passive"))
    )
    (net (code "95") (name "Net-(LED1-PadC)") (class "Default")
      (node (ref "LED1") (pin "C") (pinfunction "C_C") (pintype "passive"))
      (node (ref "T1") (pin "C") (pinfunction "C_C") (pintype "passive"))
    )
    (net (code "96") (name "Net-(LED2-PadA)") (class "Default")
      (node (ref "LED2") (pin "A") (pinfunction "A_A") (pintype "passive"))
      (node (ref "R92") (pin "1") (pinfunction "1_1") (pintype "passive"))
    )
    (net (code "97") (name "Net-(LED2-PadC)") (class "Default")
      (node (ref "LED2") (pin "C") (pinfunction "C_C") (pintype "passive"))
      (node (ref "T2") (pin "C") (pinfunction "C_C") (pintype "passive"))
    )
    (net (code "98") (name "Net-(OK1A-A)") (class "Default")
      (node (ref "OK1") (pin "1") (pinfunction "A_1") (pintype "passive"))
      (node (ref "R_CH3") (pin "2") (pinfunction "2_2") (pintype "passive"))
    )
    (net (code "99") (name "Net-(OK1B-A)") (class "Default")
      (node (ref "OK1") (pin "3") (pinfunction "A_3") (pintype "passive"))
      (node (ref "R_CH4") (pin "2") (pinfunction "2_2") (pintype "passive"))
    )
    (net (code "100") (name "Net-(OK2A-A)") (class "Default")
      (node (ref "OK2") (pin "1") (pinfunction "A_1") (pintype "passive"))
      (node (ref "R_CH1") (pin "2") (pinfunction "2_2") (pintype "passive"))
    )
    (net (code "101") (name "Net-(OK2B-A)") (class "Default")
      (node (ref "OK2") (pin "3") (pinfunction "A_3") (pintype "passive"))
      (node (ref "R_CH2") (pin "2") (pinfunction "2_2") (pintype "passive"))
    )
    (net (code "102") (name "Net-(R50-Pad2)") (class "Default")
      (node (ref "R50") (pin "2") (pinfunction "2_2") (pintype "passive"))
      (node (ref "U2") (pin "23") (pinfunction "RSVD_23") (pintype "passive"))
    )
    (net (code "103") (name "Net-(R52-Pad1)") (class "Default")
      (node (ref "R52") (pin "1") (pinfunction "1_1") (pintype "passive"))
      (node (ref "U2") (pin "41") (pinfunction "RSVD_41") (pintype "passive"))
    )
    (net (code "104") (name "Net-(R52B-1)") (class "Default")
      (node (ref "R52") (pin "2") (pinfunction "1_2") (pintype "passive"))
      (node (ref "U2") (pin "40") (pinfunction "RSVD_40") (pintype "passive"))
    )
    (net (code "105") (name "Net-(R52C-1)") (class "Default")
      (node (ref "R52") (pin "3") (pinfunction "1_3") (pintype "passive"))
      (node (ref "U2") (pin "39") (pinfunction "RSVD_39") (pintype "passive"))
    )
    (net (code "106") (name "Net-(R52D-1)") (class "Default")
      (node (ref "R52") (pin "4") (pinfunction "1_4") (pintype "passive"))
      (node (ref "U2") (pin "38") (pinfunction "RSVD_38") (pintype "passive"))
    )
    (net (code "107") (name "Net-(R53A-2)") (class "Default")
      (node (ref "R53") (pin "8") (pinfunction "2_8") (pintype "passive"))
      (node (ref "U2") (pin "42") (pinfunction "RSVD_42") (pintype "passive"))
    )
    (net (code "108") (name "Net-(R53B-2)") (class "Default")
      (node (ref "R53") (pin "7") (pinfunction "2_7") (pintype "passive"))
      (node (ref "U2") (pin "43") (pinfunction "PMODE2_43") (pintype "passive"))
    )
    (net (code "109") (name "Net-(R53C-2)") (class "Default")
      (node (ref "R53") (pin "6") (pinfunction "2_6") (pintype "passive"))
      (node (ref "U2") (pin "44") (pinfunction "PMODE1_44") (pintype "passive"))
    )
    (net (code "110") (name "Net-(R53D-2)") (class "Default")
      (node (ref "R53") (pin "5") (pinfunction "2_5") (pintype "passive"))
      (node (ref "U2") (pin "45") (pinfunction "PMODE0_45") (pintype "passive"))
    )
    (net (code "111") (name "Net-(R90-Pad1)") (class "Default")
      (node (ref "R90") (pin "1") (pinfunction "1_1") (pintype "passive"))
      (node (ref "R91") (pin "1") (pinfunction "1_1") (pintype "passive"))
      (node (ref "T2") (pin "B") (pinfunction "B_B") (pintype "passive"))
    )
    (net (code "112") (name "Net-(R93-Pad2)") (class "Default")
      (node (ref "R93") (pin "2") (pinfunction "2_2") (pintype "passive"))
      (node (ref "T3") (pin "B") (pinfunction "B_B") (pintype "passive"))
    )
    (net (code "113") (name "Net-(R95-Pad1)") (class "Default")
      (node (ref "R95") (pin "1") (pinfunction "1_1") (pintype "passive"))
      (node (ref "R96") (pin "1") (pinfunction "1_1") (pintype "passive"))
      (node (ref "T1") (pin "B") (pinfunction "B_B") (pintype "passive"))
    )
    (net (code "114") (name "Net-(RT1-Pad2)") (class "Default")
      (node (ref "RT1") (pin "2") (pinfunction "2_2") (pintype "passive"))
      (node (ref "TV16-1") (pin "IA") (pinfunction "IA_IA") (pintype "bidirectional"))
    )
    (net (code "115") (name "Net-(RT2-Pad2)") (class "Default")
      (node (ref "RT2") (pin "2") (pinfunction "2_2") (pintype "passive"))
      (node (ref "TV16-2") (pin "IA") (pinfunction "IA_IA") (pintype "bidirectional"))
    )
    (net (code "116") (name "Net-(RT3-Pad2)") (class "Default")
      (node (ref "RT3") (pin "2") (pinfunction "2_2") (pintype "passive"))
      (node (ref "TV16-3") (pin "IA") (pinfunction "IA_IA") (pintype "bidirectional"))
    )
    (net (code "117") (name "Net-(STMF401-PA2)") (class "Default")
      (node (ref "JRX") (pin "2") (pinfunction "2_2") (pintype "passive"))
      (node (ref "STMF401") (pin "16") (pinfunction "PA2_16") (pintype "bidirectional"))
    )
    (net (code "118") (name "Net-(STMF401-PA3)") (class "Default")
      (node (ref "JTX") (pin "2") (pinfunction "2_2") (pintype "passive"))
      (node (ref "STMF401") (pin "17") (pinfunction "PA3_17") (pintype "bidirectional"))
    )
    (net (code "119") (name "Net-(STMF401-PB11)") (class "Default")
      (node (ref "C28") (pin "1") (pinfunction "1_1") (pintype "passive"))
      (node (ref "STMF401") (pin "30") (pinfunction "PB11_30") (pintype "bidirectional"))
    )
    (net (code "120") (name "Net-(STMF401-PC14-OSC32_IN)") (class "Default")
      (node (ref "C22") (pin "2") (pinfunction "2_2") (pintype "passive"))
      (node (ref "STMF401") (pin "3") (pinfunction "PC14-OSC32_IN_3") (pintype "bidirectional"))
      (node (ref "XTAL1") (pin "2") (pinfunction "2_2") (pintype "passive"))
    )
    (net (code "121") (name "Net-(STMF401-PC15-OSC32_OUT)") (class "Default")
      (node (ref "C21") (pin "2") (pinfunction "2_2") (pintype "passive"))
      (node (ref "STMF401") (pin "4") (pinfunction "PC15-OSC32_OUT_4") (pintype "bidirectional"))
      (node (ref "XTAL1") (pin "1") (pinfunction "1_1") (pintype "passive"))
    )
    (net (code "122") (name "Net-(TERM_BLOCK-P$2)") (class "Default")
      (node (ref "RT2") (pin "1") (pinfunction "1_1") (pintype "passive"))
      (node (ref "TERM_BLOCK") (pin "PIN$2") (pinfunction "P$2_PIN$2") (pintype "bidirectional"))
    )
    (net (code "123") (name "Net-(TERM_BLOCK-P$3)") (class "Default")
      (node (ref "RT3") (pin "1") (pinfunction "1_1") (pintype "passive"))
      (node (ref "TERM_BLOCK") (pin "PIN$3") (pinfunction "P$3_PIN$3") (pintype "bidirectional"))
    )
    (net (code "124") (name "Net-(U$4B-DCOUPL)") (class "Default")
      (node (ref "C40") (pin "1") (pinfunction "1_1") (pintype "passive"))
      (node (ref "U$4") (pin "27") (pinfunction "DCOUPL_27") (pintype "power_in"))
    )
    (net (code "125") (name "Net-(U$4C-RBIAS)") (class "Default")
      (node (ref "RBIAS") (pin "1") (pinfunction "1_1") (pintype "passive"))
      (node (ref "U$4") (pin "23") (pinfunction "RBIAS_23") (pintype "bidirectional"))
    )
    (net (code "126") (name "Net-(U$4C-VREG-EN)") (class "Default")
      (node (ref "R_VREG") (pin "1") (pinfunction "1_1") (pintype "passive"))
      (node (ref "U$4") (pin "26") (pinfunction "VREG-EN_26") (pintype "input"))
    )
    (net (code "127") (name "Net-(U$4C-XOSC32M-Q1)") (class "Default")
      (node (ref "C44") (pin "1") (pinfunction "1_1") (pintype "passive"))
      (node (ref "U$4") (pin "13") (pinfunction "XOSC32M-Q1_13") (pintype "input"))
      (node (ref "X1") (pin "1") (pinfunction "1_1") (pintype "bidirectional"))
    )
    (net (code "128") (name "Net-(U$4C-XOSC32M-Q2)") (class "Default")
      (node (ref "C45") (pin "1") (pinfunction "1_1") (pintype "passive"))
      (node (ref "U$4") (pin "12") (pinfunction "XOSC32M-Q2_12") (pintype "output"))
      (node (ref "X1") (pin "3") (pinfunction "2_3") (pintype "bidirectional"))
    )
    (net (code "129") (name "Net-(U2-1V2O)") (class "Default")
      (node (ref "C55") (pin "1") (pinfunction "1_1") (pintype "passive"))
      (node (ref "U2") (pin "22") (pinfunction "1V2O_22") (pintype "passive"))
    )
    (net (code "130") (name "Net-(U2-EXRES1)") (class "Default")
      (node (ref "R31") (pin "2") (pinfunction "2_2") (pintype "passive"))
      (node (ref "U2") (pin "10") (pinfunction "EXRES1_10") (pintype "passive"))
    )
    (net (code "131") (name "Net-(U2-TOCAP)") (class "Default")
      (node (ref "C52") (pin "1") (pinfunction "1_1") (pintype "passive"))
      (node (ref "U2") (pin "20") (pinfunction "TOCAP_20") (pintype "passive"))
    )
    (net (code "132") (name "Net-(U2-XI{slash}CLKIN)") (class "Default")
      (node (ref "C54") (pin "1") (pinfunction "1_1") (pintype "passive"))
      (node (ref "R56") (pin "1") (pinfunction "1_1") (pintype "passive"))
      (node (ref "U2") (pin "30") (pinfunction "XI/CLKIN_30") (pintype "passive"))
      (node (ref "XTAL2") (pin "1") (pinfunction "1_1") (pintype "passive"))
    )
    (net (code "133") (name "Net-(U2-XO)") (class "Default")
      (node (ref "C57") (pin "1") (pinfunction "1_1") (pintype "passive"))
      (node (ref "R56") (pin "2") (pinfunction "2_2") (pintype "passive"))
      (node (ref "U2") (pin "31") (pinfunction "XO_31") (pintype "passive"))
      (node (ref "XTAL2") (pin "2") (pinfunction "2_2") (pintype "passive"))
    )
    (net (code "134") (name "Q1") (class "Default")
      (node (ref "IC2") (pin "15") (pinfunction "QA_15") (pintype "tri_state"))
      (node (ref "SR_OUT1") (pin "3") (pinfunction "3_3") (pintype "passive"))
    )
    (net (code "135") (name "Q2") (class "Default")
      (node (ref "IC2") (pin "1") (pinfunction "QB_1") (pintype "tri_state"))
      (node (ref "SR_OUT1") (pin "4") (pinfunction "4_4") (pintype "passive"))
    )
    (net (code "136") (name "Q3") (class "Default")
      (node (ref "IC2") (pin "2") (pinfunction "QC_2") (pintype "tri_state"))
      (node (ref "SR_OUT1") (pin "5") (pinfunction "5_5") (pintype "passive"))
    )
    (net (code "137") (name "Q4") (class "Default")
      (node (ref "IC2") (pin "3") (pinfunction "QD_3") (pintype "tri_state"))
      (node (ref "SR_OUT1") (pin "6") (pinfunction "6_6") (pintype "passive"))
    )
    (net (code "138") (name "Q5") (class "Default")
      (node (ref "IC2") (pin "4") (pinfunction "QE_4") (pintype "tri_state"))
      (node (ref "SR_OUT1") (pin "7") (pinfunction "7_7") (pintype "passive"))
    )
    (net (code "139") (name "Q6") (class "Default")
      (node (ref "IC2") (pin "5") (pinfunction "QF_5") (pintype "tri_state"))
      (node (ref "SR_OUT1") (pin "8") (pinfunction "8_8") (pintype "passive"))
    )
    (net (code "140") (name "Q7") (class "Default")
      (node (ref "IC2") (pin "6") (pinfunction "QG_6") (pintype "tri_state"))
      (node (ref "SR_OUT1") (pin "9") (pinfunction "9_9") (pintype "passive"))
    )
    (net (code "141") (name "Q8") (class "Default")
      (node (ref "IC2") (pin "7") (pinfunction "QH_7") (pintype "tri_state"))
      (node (ref "SR_OUT1") (pin "10") (pinfunction "10_10") (pintype "passive"))
    )
    (net (code "142") (name "Q9") (class "Default")
      (node (ref "IC3") (pin "15") (pinfunction "QA_15") (pintype "tri_state"))
      (node (ref "SR_OUT2") (pin "3") (pinfunction "3_3") (pintype "passive"))
    )
    (net (code "143") (name "Q10") (class "Default")
      (node (ref "IC3") (pin "1") (pinfunction "QB_1") (pintype "tri_state"))
      (node (ref "SR_OUT2") (pin "4") (pinfunction "4_4") (pintype "passive"))
    )
    (net (code "144") (name "Q11") (class "Default")
      (node (ref "IC3") (pin "2") (pinfunction "QC_2") (pintype "tri_state"))
      (node (ref "SR_OUT2") (pin "5") (pinfunction "5_5") (pintype "passive"))
    )
    (net (code "145") (name "Q12") (class "Default")
      (node (ref "IC3") (pin "3") (pinfunction "QD_3") (pintype "tri_state"))
      (node (ref "SR_OUT2") (pin "6") (pinfunction "6_6") (pintype "passive"))
    )
    (net (code "146") (name "Q13") (class "Default")
      (node (ref "IC3") (pin "4") (pinfunction "QE_4") (pintype "tri_state"))
      (node (ref "SR_OUT2") (pin "7") (pinfunction "7_7") (pintype "passive"))
    )
    (net (code "147") (name "Q14") (class "Default")
      (node (ref "IC3") (pin "5") (pinfunction "QF_5") (pintype "tri_state"))
      (node (ref "SR_OUT2") (pin "8") (pinfunction "8_8") (pintype "passive"))
    )
    (net (code "148") (name "Q15") (class "Default")
      (node (ref "IC3") (pin "6") (pinfunction "QG_6") (pintype "tri_state"))
      (node (ref "SR_OUT2") (pin "9") (pinfunction "9_9") (pintype "passive"))
    )
    (net (code "149") (name "Q16") (class "Default")
      (node (ref "IC3") (pin "7") (pinfunction "QH_7") (pintype "tri_state"))
      (node (ref "SR_OUT2") (pin "10") (pinfunction "10_10") (pintype "passive"))
    )
    (net (code "150") (name "QS") (class "Default")
      (node (ref "IC2") (pin "9") (pinfunction "QH*_9") (pintype "tri_state"))
      (node (ref "IC3") (pin "14") (pinfunction "SER_14") (pintype "input"))
    )
    (net (code "151") (name "QS2") (class "Default")
      (node (ref "IC3") (pin "9") (pinfunction "QH*_9") (pintype "tri_state"))
      (node (ref "IC5") (pin "14") (pinfunction "SER_14") (pintype "input"))
    )
    (net (code "152") (name "R") (class "Default")
      (node (ref "HLK-PM01") (pin "AC$1") (pinfunction "AC_IN$1_AC$1") (pintype "bidirectional"))
      (node (ref "RT1") (pin "1") (pinfunction "1_1") (pintype "passive"))
      (node (ref "TERM_BLOCK") (pin "PIN$1") (pinfunction "P$1_PIN$1") (pintype "bidirectional"))
    )
    (net (code "153") (name "RXN") (class "Default")
      (node (ref "C34") (pin "2") (pinfunction "2_2") (pintype "passive"))
      (node (ref "R32") (pin "1") (pinfunction "1_1") (pintype "passive"))
      (node (ref "U2") (pin "5") (pinfunction "RXN_5") (pintype "passive"))
    )
    (net (code "154") (name "RXP") (class "Default")
      (node (ref "C32") (pin "2") (pinfunction "2_2") (pintype "passive"))
      (node (ref "R30") (pin "2") (pinfunction "2_2") (pintype "passive"))
      (node (ref "U2") (pin "6") (pinfunction "RXP_6") (pintype "passive"))
    )
    (net (code "155") (name "SD_CS") (class "Default")
      (node (ref "LCD14") (pin "SD_CS") (pinfunction "SD_CS_SD_CS") (pintype "bidirectional"))
      (node (ref "STMF401") (pin "55") (pinfunction "PB3_55") (pintype "bidirectional"))
    )
    (net (code "156") (name "SERIAL_RX") (class "Default")
      (node (ref "STM-USART") (pin "3") (pinfunction "3_3") (pintype "passive"))
      (node (ref "STMF401") (pin "43") (pinfunction "PA10_43") (pintype "bidirectional"))
    )
    (net (code "157") (name "SERIAL_TX") (class "Default")
      (node (ref "STM-USART") (pin "2") (pinfunction "2_2") (pintype "passive"))
      (node (ref "STMF401") (pin "42") (pinfunction "PA9_42") (pintype "bidirectional"))
    )
    (net (code "158") (name "SIM900_PWRKEY") (class "Default")
      (node (ref "IC1") (pin "P$1") (pinfunction "PWRKEY_P$1") (pintype "power_in"))
      (node (ref "T3") (pin "C") (pinfunction "C_C") (pintype "passive"))
    )
    (net (code "159") (name "SIM_NETLIGHT") (class "Default")
      (node (ref "IC1") (pin "P$52") (pinfunction "NETLIGHT_P$52") (pintype "bidirectional"))
      (node (ref "R91") (pin "2") (pinfunction "2_2") (pintype "passive"))
    )
    (net (code "160") (name "SIM_PWRKEY") (class "Default")
      (node (ref "R93") (pin "1") (pinfunction "1_1") (pintype "passive"))
      (node (ref "STMF401") (pin "41") (pinfunction "PA8_41") (pintype "bidirectional"))
    )
    (net (code "161") (name "SIM_RX") (class "Default")
      (node (ref "IC1") (pin "P$10") (pinfunction "RXD_P$10") (pintype "input"))
      (node (ref "STMF401") (pin "51") (pinfunction "PC10_51") (pintype "bidirectional"))
    )
    (net (code "162") (name "SIM_STATUS") (class "Default")
      (node (ref "IC1") (pin "P$66") (pinfunction "STATUS_P$66") (pintype "bidirectional"))
      (node (ref "R95") (pin "2") (pinfunction "2_2") (pintype "passive"))
    )
    (net (code "163") (name "SIM_TX") (class "Default")
      (node (ref "IC1") (pin "P$9") (pinfunction "TXD_P$9") (pintype "output"))
      (node (ref "STMF401") (pin "50") (pinfunction "PA15_50") (pintype "bidirectional"))
    )
    (net (code "164") (name "SR_DS") (class "Default")
      (node (ref "IC2") (pin "14") (pinfunction "SER_14") (pintype "input"))
      (node (ref "STMF401") (pin "8") (pinfunction "PC0_8") (pintype "bidirectional"))
    )
    (net (code "165") (name "SR_RST") (class "Default")
      (node (ref "IC2") (pin "10") (pinfunction "SCL_10") (pintype "input"))
      (node (ref "IC3") (pin "10") (pinfunction "SCL_10") (pintype "input"))
      (node (ref "IC5") (pin "10") (pinfunction "SCL_10") (pintype "input"))
      (node (ref "STMF401") (pin "11") (pinfunction "PC3_11") (pintype "bidirectional"))
    )
    (net (code "166") (name "SR_SHCP") (class "Default")
      (node (ref "IC2") (pin "11") (pinfunction "SCK_11") (pintype "input"))
      (node (ref "IC3") (pin "11") (pinfunction "SCK_11") (pintype "input"))
      (node (ref "IC5") (pin "11") (pinfunction "SCK_11") (pintype "input"))
      (node (ref "STMF401") (pin "10") (pinfunction "PC2_10") (pintype "bidirectional"))
    )
    (net (code "167") (name "SR_STCP") (class "Default")
      (node (ref "IC2") (pin "12") (pinfunction "RCK_12") (pintype "input"))
      (node (ref "IC3") (pin "12") (pinfunction "RCK_12") (pintype "input"))
      (node (ref "IC5") (pin "12") (pinfunction "RCK_12") (pintype "input"))
      (node (ref "STMF401") (pin "9") (pinfunction "PC1_9") (pintype "bidirectional"))
    )
    (net (code "168") (name "SWD_NRST") (class "Default")
      (node (ref "C20") (pin "1") (pinfunction "1_1") (pintype "passive"))
      (node (ref "S1") (pin "1") (pinfunction "1_1") (pintype "passive"))
      (node (ref "S1") (pin "2") (pinfunction "2_2") (pintype "passive"))
      (node (ref "STMF401") (pin "7") (pinfunction "NRST_7") (pintype "bidirectional"))
    )
    (net (code "169") (name "SWD_TCK") (class "Default")
      (node (ref "STM-SWD") (pin "2") (pinfunction "2_2") (pintype "passive"))
      (node (ref "STMF401") (pin "49") (pinfunction "PA14_49") (pintype "bidirectional"))
    )
    (net (code "170") (name "SWD_TMS") (class "Default")
      (node (ref "STM-SWD") (pin "4") (pinfunction "4_4") (pintype "passive"))
      (node (ref "STMF401") (pin "46") (pinfunction "PA13_46") (pintype "bidirectional"))
    )
    (net (code "171") (name "TXN") (class "Default")
      (node (ref "ETHERNET") (pin "2") (pinfunction "TX-_2") (pintype "bidirectional"))
      (node (ref "R34") (pin "1") (pinfunction "1_1") (pintype "passive"))
      (node (ref "U2") (pin "1") (pinfunction "TXN_1") (pintype "passive"))
    )
    (net (code "172") (name "TXP") (class "Default")
      (node (ref "ETHERNET") (pin "1") (pinfunction "TX+_1") (pintype "bidirectional"))
      (node (ref "R35") (pin "1") (pinfunction "1_1") (pintype "passive"))
      (node (ref "U2") (pin "2") (pinfunction "TXP_2") (pintype "passive"))
    )
    (net (code "173") (name "T_CLK") (class "Default")
      (node (ref "LCD14") (pin "T_CLK") (pinfunction "T_CLK_T_CLK") (pintype "bidirectional"))
      (node (ref "STMF401") (pin "27") (pinfunction "PB1_27") (pintype "bidirectional"))
    )
    (net (code "174") (name "T_DIN") (class "Default")
      (node (ref "LCD14") (pin "T_DIN") (pinfunction "T_DIN_T_DIN") (pintype "bidirectional"))
      (node (ref "STMF401") (pin "29") (pinfunction "PB10_29") (pintype "bidirectional"))
    )
    (net (code "175") (name "T_DO") (class "Default")
      (node (ref "LCD14") (pin "T_DO") (pinfunction "T_DO_T_DO") (pintype "bidirectional"))
      (node (ref "STMF401") (pin "26") (pinfunction "PB0_26") (pintype "bidirectional"))
    )
    (net (code "176") (name "T_IRQ") (class "Default")
      (node (ref "LCD14") (pin "T_IRQ") (pinfunction "T_IRQ_T_IRQ") (pintype "bidirectional"))
      (node (ref "STMF401") (pin "28") (pinfunction "PB2_28") (pintype "bidirectional"))
    )
    (net (code "177") (name "USB_DM") (class "Default")
      (node (ref "STMF401") (pin "44") (pinfunction "PA11_44") (pintype "bidirectional"))
      (node (ref "USB_IN") (pin "D-1") (pinfunction "D-_D-1") (pintype "bidirectional"))
    )
    (net (code "178") (name "USB_DP") (class "Default")
      (node (ref "STMF401") (pin "45") (pinfunction "PA12_45") (pintype "bidirectional"))
      (node (ref "USB_IN") (pin "D+1") (pinfunction "D+_D+1") (pintype "bidirectional"))
    )
    (net (code "179") (name "USIM_CLK") (class "Default")
      (node (ref "SIM900-R2") (pin "2") (pinfunction "2_2") (pintype "passive"))
      (node (ref "SIMHOLDER") (pin "SIM_CLK") (pinfunction "SIM_CLK_SIM_CLK") (pintype "bidirectional"))
    )
    (net (code "180") (name "USIM_DATA") (class "Default")
      (node (ref "SIM900-R3") (pin "2") (pinfunction "2_2") (pintype "passive"))
      (node (ref "SIMHOLDER") (pin "SIM_IO") (pinfunction "SIM_IO_SIM_IO") (pintype "bidirectional"))
    )
    (net (code "181") (name "USIM_RESET") (class "Default")
      (node (ref "SIM900-R1") (pin "2") (pinfunction "2_2") (pintype "passive"))
      (node (ref "SIMHOLDER") (pin "SIM_RST") (pinfunction "SIM_RST_SIM_RST") (pintype "bidirectional"))
    )
    (net (code "182") (name "USIM_VCC") (class "Default")
      (node (ref "C80") (pin "2") (pinfunction "2_2") (pintype "passive"))
      (node (ref "C81") (pin "2") (pinfunction "2_2") (pintype "passive"))
      (node (ref "IC1") (pin "P$30") (pinfunction "SIM_VDD_P$30") (pintype "power_in"))
      (node (ref "SIM900-C4") (pin "1") (pinfunction "1_1") (pintype "passive"))
      (node (ref "SIM900-C5") (pin "1") (pinfunction "1_1") (pintype "passive"))
      (node (ref "SIMHOLDER") (pin "SIM_VDD") (pinfunction "SIM_VDD_SIM_VDD") (pintype "bidirectional"))
    )
    (net (code "183") (name "VBAT") (class "Default")
      (node (ref "BAT1") (pin "PWR@1") (pinfunction "+_PWR@1") (pintype "power_in"))
      (node (ref "STMF401") (pin "1") (pinfunction "VLCD_1") (pintype "power_in"))
    )
    (net (code "184") (name "VCC") (class "Default")
      (node (ref "C11") (pin "1") (pinfunction "1_1") (pintype "passive"))
      (node (ref "C25") (pin "1") (pinfunction "1_1") (pintype "passive"))
      (node (ref "C31") (pin "1") (pinfunction "1_1") (pintype "passive"))
      (node (ref "C33") (pin "1") (pinfunction "1_1") (pintype "passive"))
      (node (ref "C35") (pin "1") (pinfunction "1_1") (pintype "passive"))
      (node (ref "C37") (pin "+") (pinfunction "+_+") (pintype "passive"))
      (node (ref "C50") (pin "1") (pinfunction "1_1") (pintype "passive"))
      (node (ref "C51") (pin "1") (pinfunction "1_1") (pintype "passive"))
      (node (ref "C53") (pin "1") (pinfunction "1_1") (pintype "passive"))
      (node (ref "L3") (pin "2") (pinfunction "2_2") (pintype "passive"))
      (node (ref "R10") (pin "2") (pinfunction "2_2") (pintype "passive"))
      (node (ref "R33") (pin "2") (pinfunction "2_2") (pintype "passive"))
      (node (ref "R34") (pin "2") (pinfunction "2_2") (pintype "passive"))
      (node (ref "R35") (pin "2") (pinfunction "2_2") (pintype "passive"))
      (node (ref "STMF401") (pin "13") (pinfunction "VDDA_13") (pintype "power_in"))
      (node (ref "U2") (pin "11") (pinfunction "AVDD_11") (pintype "passive"))
      (node (ref "U2") (pin "15") (pinfunction "AVDD_15") (pintype "passive"))
      (node (ref "U2") (pin "17") (pinfunction "AVDD_17") (pintype "passive"))
      (node (ref "U2") (pin "21") (pinfunction "AVDD_21") (pintype "passive"))
      (node (ref "U2") (pin "4") (pinfunction "AVDD_4") (pintype "passive"))
      (node (ref "U2") (pin "8") (pinfunction "AVDD_8") (pintype "passive"))
    )
    (net (code "185") (name "VDD") (class "Default")
      (node (ref "C10") (pin "1") (pinfunction "1_1") (pintype "passive"))
      (node (ref "C23") (pin "2") (pinfunction "2_2") (pintype "passive"))
      (node (ref "C24") (pin "1") (pinfunction "1_1") (pintype "passive"))
      (node (ref "C26") (pin "1") (pinfunction "1_1") (pintype "passive"))
      (node (ref "C27") (pin "1") (pinfunction "1_1") (pintype "passive"))
      (node (ref "C41") (pin "1") (pinfunction "1_1") (pintype "passive"))
      (node (ref "C43") (pin "1") (pinfunction "1_1") (pintype "passive"))
      (node (ref "C46") (pin "1") (pinfunction "1_1") (pintype "passive"))
      (node (ref "C56") (pin "1") (pinfunction "1_1") (pintype "passive"))
      (node (ref "DHT-R1") (pin "1") (pinfunction "1_1") (pintype "passive"))
      (node (ref "ESP_EXT") (pin "1") (pinfunction "1_1") (pintype "passive"))
      (node (ref "ETHERNET") (pin "12") (pinfunction "LED2_A_12") (pintype "bidirectional"))
      (node (ref "ETHERNET") (pin "9") (pinfunction "LED1_A_9") (pintype "bidirectional"))
      (node (ref "IC2") (pin "16") (pinfunction "VCC_16") (pintype "power_in"))
      (node (ref "IC3") (pin "16") (pinfunction "VCC_16") (pintype "power_in"))
      (node (ref "IC5") (pin "16") (pinfunction "VCC_16") (pintype "power_in"))
      (node (ref "L2") (pin "2") (pinfunction "2_2") (pintype "passive"))
      (node (ref "L3") (pin "1") (pinfunction "1_1") (pintype "passive"))
      (node (ref "LCD-R1") (pin "2") (pinfunction "2_2") (pintype "passive"))
      (node (ref "LCD14") (pin "LCD_VCC") (pinfunction "LCD_VCC_LCD_VCC") (pintype "power_in"))
      (node (ref "LCD_C1") (pin "1") (pinfunction "1_1") (pintype "passive"))
      (node (ref "PWR") (pin "1") (pinfunction "1_1") (pintype "passive"))
      (node (ref "R10") (pin "1") (pinfunction "1_1") (pintype "passive"))
      (node (ref "R51") (pin "1") (pinfunction "1_1") (pintype "passive"))
      (node (ref "R53") (pin "2") (pinfunction "1_2") (pintype "passive"))
      (node (ref "R53") (pin "3") (pinfunction "1_3") (pintype "passive"))
      (node (ref "R53") (pin "4") (pinfunction "1_4") (pintype "passive"))
      (node (ref "R54") (pin "2") (pinfunction "2_2") (pintype "passive"))
      (node (ref "R92") (pin "2") (pinfunction "2_2") (pintype "passive"))
      (node (ref "R94") (pin "2") (pinfunction "2_2") (pintype "passive"))
      (node (ref "R_VREG") (pin "2") (pinfunction "2_2") (pintype "passive"))
      (node (ref "STM-C13") (pin "1") (pinfunction "1_1") (pintype "passive"))
      (node (ref "STM-SWD") (pin "1") (pinfunction "1_1") (pintype "passive"))
      (node (ref "STM-USART") (pin "1") (pinfunction "1_1") (pintype "passive"))
      (node (ref "STMF401") (pin "19") (pinfunction "VDD_4_19") (pintype "power_in"))
      (node (ref "STMF401") (pin "32") (pinfunction "VDD_1_32") (pintype "power_in"))
      (node (ref "STMF401") (pin "48") (pinfunction "VDD_2_48") (pintype "power_in"))
      (node (ref "STMF401") (pin "64") (pinfunction "VDD_3_64") (pintype "power_in"))
      (node (ref "U$17") (pin "VCC") (pinfunction "VCC_VCC") (pintype "bidirectional"))
      (node (ref "U$4") (pin "11") (pinfunction "AVDD_11") (pintype "power_in"))
      (node (ref "U$4") (pin "14") (pinfunction "AVDD_14") (pintype "power_in"))
      (node (ref "U$4") (pin "16") (pinfunction "AVDD_16") (pintype "power_in"))
      (node (ref "U$4") (pin "20") (pinfunction "AVDD_20") (pintype "power_in"))
      (node (ref "U$4") (pin "22") (pinfunction "AVDD_22") (pintype "power_in"))
      (node (ref "U$4") (pin "24") (pinfunction "AVDD-GUARD_24") (pintype "power_in"))
      (node (ref "U$4") (pin "8") (pinfunction "DVDD_8") (pintype "power_in"))
      (node (ref "U2") (pin "28") (pinfunction "VDD_28") (pintype "passive"))
      (node (ref "W5500-C13") (pin "+") (pinfunction "+_+") (pintype "passive"))
    )
    (net (code "186") (name "VESP") (class "Default")
      (node (ref "ESP") (pin "CH_PD") (pinfunction "CH_PD_CH_PD") (pintype "bidirectional"))
      (node (ref "ESP") (pin "GPIO02") (pinfunction "GPIO2_GPIO02") (pintype "bidirectional"))
      (node (ref "ESP") (pin "REST") (pinfunction "REST_REST") (pintype "bidirectional"))
      (node (ref "ESP") (pin "VCC") (pinfunction "VCC_VCC") (pintype "power_in"))
      (node (ref "ESP-C1") (pin "1") (pinfunction "1_1") (pintype "passive"))
      (node (ref "ESP-GPIO0") (pin "1") (pinfunction "1_1") (pintype "passive"))
      (node (ref "ESP_EXT") (pin "2") (pinfunction "2_2") (pintype "passive"))
    )
    (net (code "187") (name "unconnected-(ESP-GPIO4-PadGPIO04)") (class "Default")
      (node (ref "ESP") (pin "GPIO04") (pinfunction "GPIO4_GPIO04") (pintype "bidirectional"))
    )
    (net (code "188") (name "unconnected-(ESP-GPIO5-PadGPIO05)") (class "Default")
      (node (ref "ESP") (pin "GPIO05") (pinfunction "GPIO5_GPIO05") (pintype "bidirectional"))
    )
    (net (code "189") (name "unconnected-(ESP-PadADC)") (class "Default")
      (node (ref "ESP") (pin "ADC") (pinfunction "ADC_ADC") (pintype "bidirectional"))
    )
    (net (code "190") (name "unconnected-(ESP-PadGPIO12)") (class "Default")
      (node (ref "ESP") (pin "GPIO12") (pinfunction "GPIO12_GPIO12") (pintype "bidirectional"))
    )
    (net (code "191") (name "unconnected-(ESP-PadGPIO13)") (class "Default")
      (node (ref "ESP") (pin "GPIO13") (pinfunction "GPIO13_GPIO13") (pintype "bidirectional"))
    )
    (net (code "192") (name "unconnected-(ESP-PadGPIO14)") (class "Default")
      (node (ref "ESP") (pin "GPIO14") (pinfunction "GPIO14_GPIO14") (pintype "bidirectional"))
    )
    (net (code "193") (name "unconnected-(ESP-PadGPIO16)") (class "Default")
      (node (ref "ESP") (pin "GPIO16") (pinfunction "GPIO16_GPIO16") (pintype "bidirectional"))
    )
    (net (code "194") (name "unconnected-(IC1-ADC-PadP$25)") (class "Default")
      (node (ref "IC1") (pin "P$25") (pinfunction "ADC_P$25") (pintype "bidirectional"))
    )
    (net (code "195") (name "unconnected-(IC1-CTS-PadP$7)") (class "Default")
      (node (ref "IC1") (pin "P$7") (pinfunction "CTS_P$7") (pintype "output"))
    )
    (net (code "196") (name "unconnected-(IC1-DBG_RXD-PadP$28)") (class "Default")
      (node (ref "IC1") (pin "P$28") (pinfunction "DBG_RXD_P$28") (pintype "input"))
    )
    (net (code "197") (name "unconnected-(IC1-DBG_TXD-PadP$27)") (class "Default")
      (node (ref "IC1") (pin "P$27") (pinfunction "DBG_TXD_P$27") (pintype "output"))
    )
    (net (code "198") (name "unconnected-(IC1-DCD-PadP$5)") (class "Default")
      (node (ref "IC1") (pin "P$5") (pinfunction "DCD_P$5") (pintype "output"))
    )
    (net (code "199") (name "unconnected-(IC1-DISP_CLK-PadP$11)") (class "Default")
      (node (ref "IC1") (pin "P$11") (pinfunction "DISP_CLK_P$11") (pintype "bidirectional"))
    )
    (net (code "200") (name "unconnected-(IC1-DISP_CS-PadP$14)") (class "Default")
      (node (ref "IC1") (pin "P$14") (pinfunction "DISP_CS_P$14") (pintype "bidirectional"))
    )
    (net (code "201") (name "unconnected-(IC1-DISP_DATA-PadP$12)") (class "Default")
      (node (ref "IC1") (pin "P$12") (pinfunction "DISP_DATA_P$12") (pintype "bidirectional"))
    )
    (net (code "202") (name "unconnected-(IC1-DISP_DC-PadP$13)") (class "Default")
      (node (ref "IC1") (pin "P$13") (pinfunction "DISP_DC_P$13") (pintype "bidirectional"))
    )
    (net (code "203") (name "unconnected-(IC1-DTR-PadP$3)") (class "Default")
      (node (ref "IC1") (pin "P$3") (pinfunction "DTR_P$3") (pintype "input"))
    )
    (net (code "204") (name "unconnected-(IC1-GPIO1{slash}KBR4-PadP$40)") (class "Default")
      (node (ref "IC1") (pin "P$40") (pinfunction "GPIO1/KBR4_P$40") (pintype "bidirectional"))
    )
    (net (code "205") (name "unconnected-(IC1-GPIO2{slash}KBR3-PadP$41)") (class "Default")
      (node (ref "IC1") (pin "P$41") (pinfunction "GPIO2/KBR3_P$41") (pintype "bidirectional"))
    )
    (net (code "206") (name "unconnected-(IC1-GPIO3{slash}KBR2-PadP$42)") (class "Default")
      (node (ref "IC1") (pin "P$42") (pinfunction "GPIO3/KBR2_P$42") (pintype "bidirectional"))
    )
    (net (code "207") (name "unconnected-(IC1-GPIO4{slash}KBR1-PadP$43)") (class "Default")
      (node (ref "IC1") (pin "P$43") (pinfunction "GPIO4/KBR1_P$43") (pintype "bidirectional"))
    )
    (net (code "208") (name "unconnected-(IC1-GPIO5{slash}KBR0-PadP$44)") (class "Default")
      (node (ref "IC1") (pin "P$44") (pinfunction "GPIO5/KBR0_P$44") (pintype "bidirectional"))
    )
    (net (code "209") (name "unconnected-(IC1-GPIO6{slash}KBC4-PadP$47)") (class "Default")
      (node (ref "IC1") (pin "P$47") (pinfunction "GPIO6/KBC4_P$47") (pintype "bidirectional"))
    )
    (net (code "210") (name "unconnected-(IC1-GPIO7{slash}KBC3-PadP$48)") (class "Default")
      (node (ref "IC1") (pin "P$48") (pinfunction "GPIO7/KBC3_P$48") (pintype "bidirectional"))
    )
    (net (code "211") (name "unconnected-(IC1-GPIO8{slash}KBC2-PadP$49)") (class "Default")
      (node (ref "IC1") (pin "P$49") (pinfunction "GPIO8/KBC2_P$49") (pintype "bidirectional"))
    )
    (net (code "212") (name "unconnected-(IC1-GPIO9{slash}KBC1-PadP$50)") (class "Default")
      (node (ref "IC1") (pin "P$50") (pinfunction "GPIO9/KBC1_P$50") (pintype "bidirectional"))
    )
    (net (code "213") (name "unconnected-(IC1-GPIO10-PadP$51)") (class "Default")
      (node (ref "IC1") (pin "P$51") (pinfunction "GPIO10_P$51") (pintype "bidirectional"))
    )
    (net (code "214") (name "unconnected-(IC1-LINEIN_L-PadP$24)") (class "Default")
      (node (ref "IC1") (pin "P$24") (pinfunction "LINEIN_L_P$24") (pintype "bidirectional"))
    )
    (net (code "215") (name "unconnected-(IC1-LINEIN_R-PadP$23)") (class "Default")
      (node (ref "IC1") (pin "P$23") (pinfunction "LINEIN_R_P$23") (pintype "bidirectional"))
    )
    (net (code "216") (name "unconnected-(IC1-MIC_N-PadP$20)") (class "Default")
      (node (ref "IC1") (pin "P$20") (pinfunction "MIC_N_P$20") (pintype "bidirectional"))
    )
    (net (code "217") (name "unconnected-(IC1-MIC_P-PadP$19)") (class "Default")
      (node (ref "IC1") (pin "P$19") (pinfunction "MIC_P_P$19") (pintype "bidirectional"))
    )
    (net (code "218") (name "unconnected-(IC1-NC-PadP$2)") (class "Default")
      (node (ref "IC1") (pin "P$2") (pinfunction "NC_P$2") (pintype "no_connect"))
    )
    (net (code "219") (name "unconnected-(IC1-NC-PadP$6)") (class "Default")
      (node (ref "IC1") (pin "P$6") (pinfunction "NC_P$6") (pintype "no_connect"))
    )
    (net (code "220") (name "unconnected-(IC1-NRESET-PadP$16)") (class "Default")
      (node (ref "IC1") (pin "P$16") (pinfunction "NRESET_P$16") (pintype "bidirectional"))
    )
    (net (code "221") (name "unconnected-(IC1-PWM1-PadP$35)") (class "Default")
      (node (ref "IC1") (pin "P$35") (pinfunction "PWM1_P$35") (pintype "bidirectional"))
    )
    (net (code "222") (name "unconnected-(IC1-PWM2-PadP$36)") (class "Default")
      (node (ref "IC1") (pin "P$36") (pinfunction "PWM2_P$36") (pintype "bidirectional"))
    )
    (net (code "223") (name "unconnected-(IC1-RI-PadP$4)") (class "Default")
      (node (ref "IC1") (pin "P$4") (pinfunction "RI_P$4") (pintype "output"))
    )
    (net (code "224") (name "unconnected-(IC1-RTS-PadP$8)") (class "Default")
      (node (ref "IC1") (pin "P$8") (pinfunction "RTS_P$8") (pintype "input"))
    )
    (net (code "225") (name "unconnected-(IC1-SCL-PadP$38)") (class "Default")
      (node (ref "IC1") (pin "P$38") (pinfunction "SCL_P$38") (pintype "bidirectional"))
    )
    (net (code "226") (name "unconnected-(IC1-SDA-PadP$37)") (class "Default")
      (node (ref "IC1") (pin "P$37") (pinfunction "SDA_P$37") (pintype "bidirectional"))
    )
    (net (code "227") (name "unconnected-(IC1-SIM_PRESENCE-PadP$34)") (class "Default")
      (node (ref "IC1") (pin "P$34") (pinfunction "SIM_PRESENCE_P$34") (pintype "bidirectional"))
    )
    (net (code "228") (name "unconnected-(IC1-SPK_N-PadP$22)") (class "Default")
      (node (ref "IC1") (pin "P$22") (pinfunction "SPK_N_P$22") (pintype "bidirectional"))
    )
    (net (code "229") (name "unconnected-(IC1-SPK_P-PadP$21)") (class "Default")
      (node (ref "IC1") (pin "P$21") (pinfunction "SPK_P_P$21") (pintype "bidirectional"))
    )
    (net (code "230") (name "unconnected-(IC1-VDD_EXT-PadP$15)") (class "Default")
      (node (ref "IC1") (pin "P$15") (pinfunction "VDD_EXT_P$15") (pintype "bidirectional"))
    )
    (net (code "231") (name "unconnected-(IC5A-QE-Pad4)") (class "Default")
      (node (ref "IC5") (pin "4") (pinfunction "QE_4") (pintype "tri_state"))
    )
    (net (code "232") (name "unconnected-(IC5A-QF-Pad5)") (class "Default")
      (node (ref "IC5") (pin "5") (pinfunction "QF_5") (pintype "tri_state"))
    )
    (net (code "233") (name "unconnected-(IC5A-QG-Pad6)") (class "Default")
      (node (ref "IC5") (pin "6") (pinfunction "QG_6") (pintype "tri_state"))
    )
    (net (code "234") (name "unconnected-(IC5A-QH*-Pad9)") (class "Default")
      (node (ref "IC5") (pin "9") (pinfunction "QH*_9") (pintype "tri_state"))
    )
    (net (code "235") (name "unconnected-(IC5A-QH-Pad7)") (class "Default")
      (node (ref "IC5") (pin "7") (pinfunction "QH_7") (pintype "tri_state"))
    )
    (net (code "236") (name "unconnected-(SIMHOLDER-PadVPP)") (class "Default")
      (node (ref "SIMHOLDER") (pin "VPP") (pinfunction "VPP_VPP") (pintype "bidirectional"))
    )
    (net (code "237") (name "unconnected-(STMF401-BOOT0-Pad60)") (class "Default")
      (node (ref "STMF401") (pin "60") (pinfunction "BOOT0_60") (pintype "input"))
    )
    (net (code "238") (name "unconnected-(U$17-PadNO)") (class "Default")
      (node (ref "U$17") (pin "NO") (pinfunction "NO_NO") (pintype "bidirectional"))
    )
    (net (code "239") (name "unconnected-(U2-DNC-Pad7)") (class "Default")
      (node (ref "U2") (pin "7") (pinfunction "DNC_7") (pintype "passive"))
    )
    (net (code "240") (name "unconnected-(U2-DUPLED-Pad26)") (class "Default")
      (node (ref "U2") (pin "26") (pinfunction "DUPLED_26") (pintype "passive"))
    )
    (net (code "241") (name "unconnected-(U2-INT_N-Pad36)") (class "Default")
      (node (ref "U2") (pin "36") (pinfunction "INT_N_36") (pintype "passive"))
    )
    (net (code "242") (name "unconnected-(U2-NC-Pad12)") (class "Default")
      (node (ref "U2") (pin "12") (pinfunction "NC_12") (pintype "passive"))
    )
    (net (code "243") (name "unconnected-(U2-NC-Pad13)") (class "Default")
      (node (ref "U2") (pin "13") (pinfunction "NC_13") (pintype "passive"))
    )
    (net (code "244") (name "unconnected-(U2-NC-Pad46)") (class "Default")
      (node (ref "U2") (pin "46") (pinfunction "NC_46") (pintype "passive"))
    )
    (net (code "245") (name "unconnected-(U2-NC-Pad47)") (class "Default")
      (node (ref "U2") (pin "47") (pinfunction "NC_47") (pintype "passive"))
    )
    (net (code "246") (name "unconnected-(U2-SPDLED-Pad24)") (class "Default")
      (node (ref "U2") (pin "24") (pinfunction "SPDLED_24") (pintype "passive"))
    )
    (net (code "247") (name "unconnected-(U2-VBG-Pad18)") (class "Default")
      (node (ref "U2") (pin "18") (pinfunction "VBG_18") (pintype "passive"))
    )
    (net (code "248") (name "unconnected-(USB_IN-ID-PadID1)") (class "Default")
      (node (ref "USB_IN") (pin "ID1") (pinfunction "ID_ID1") (pintype "bidirectional"))
    )
  )
)
